# SM3320-BATT-EV.net
KiCad netlist of a schematic drawn in Altium Designer
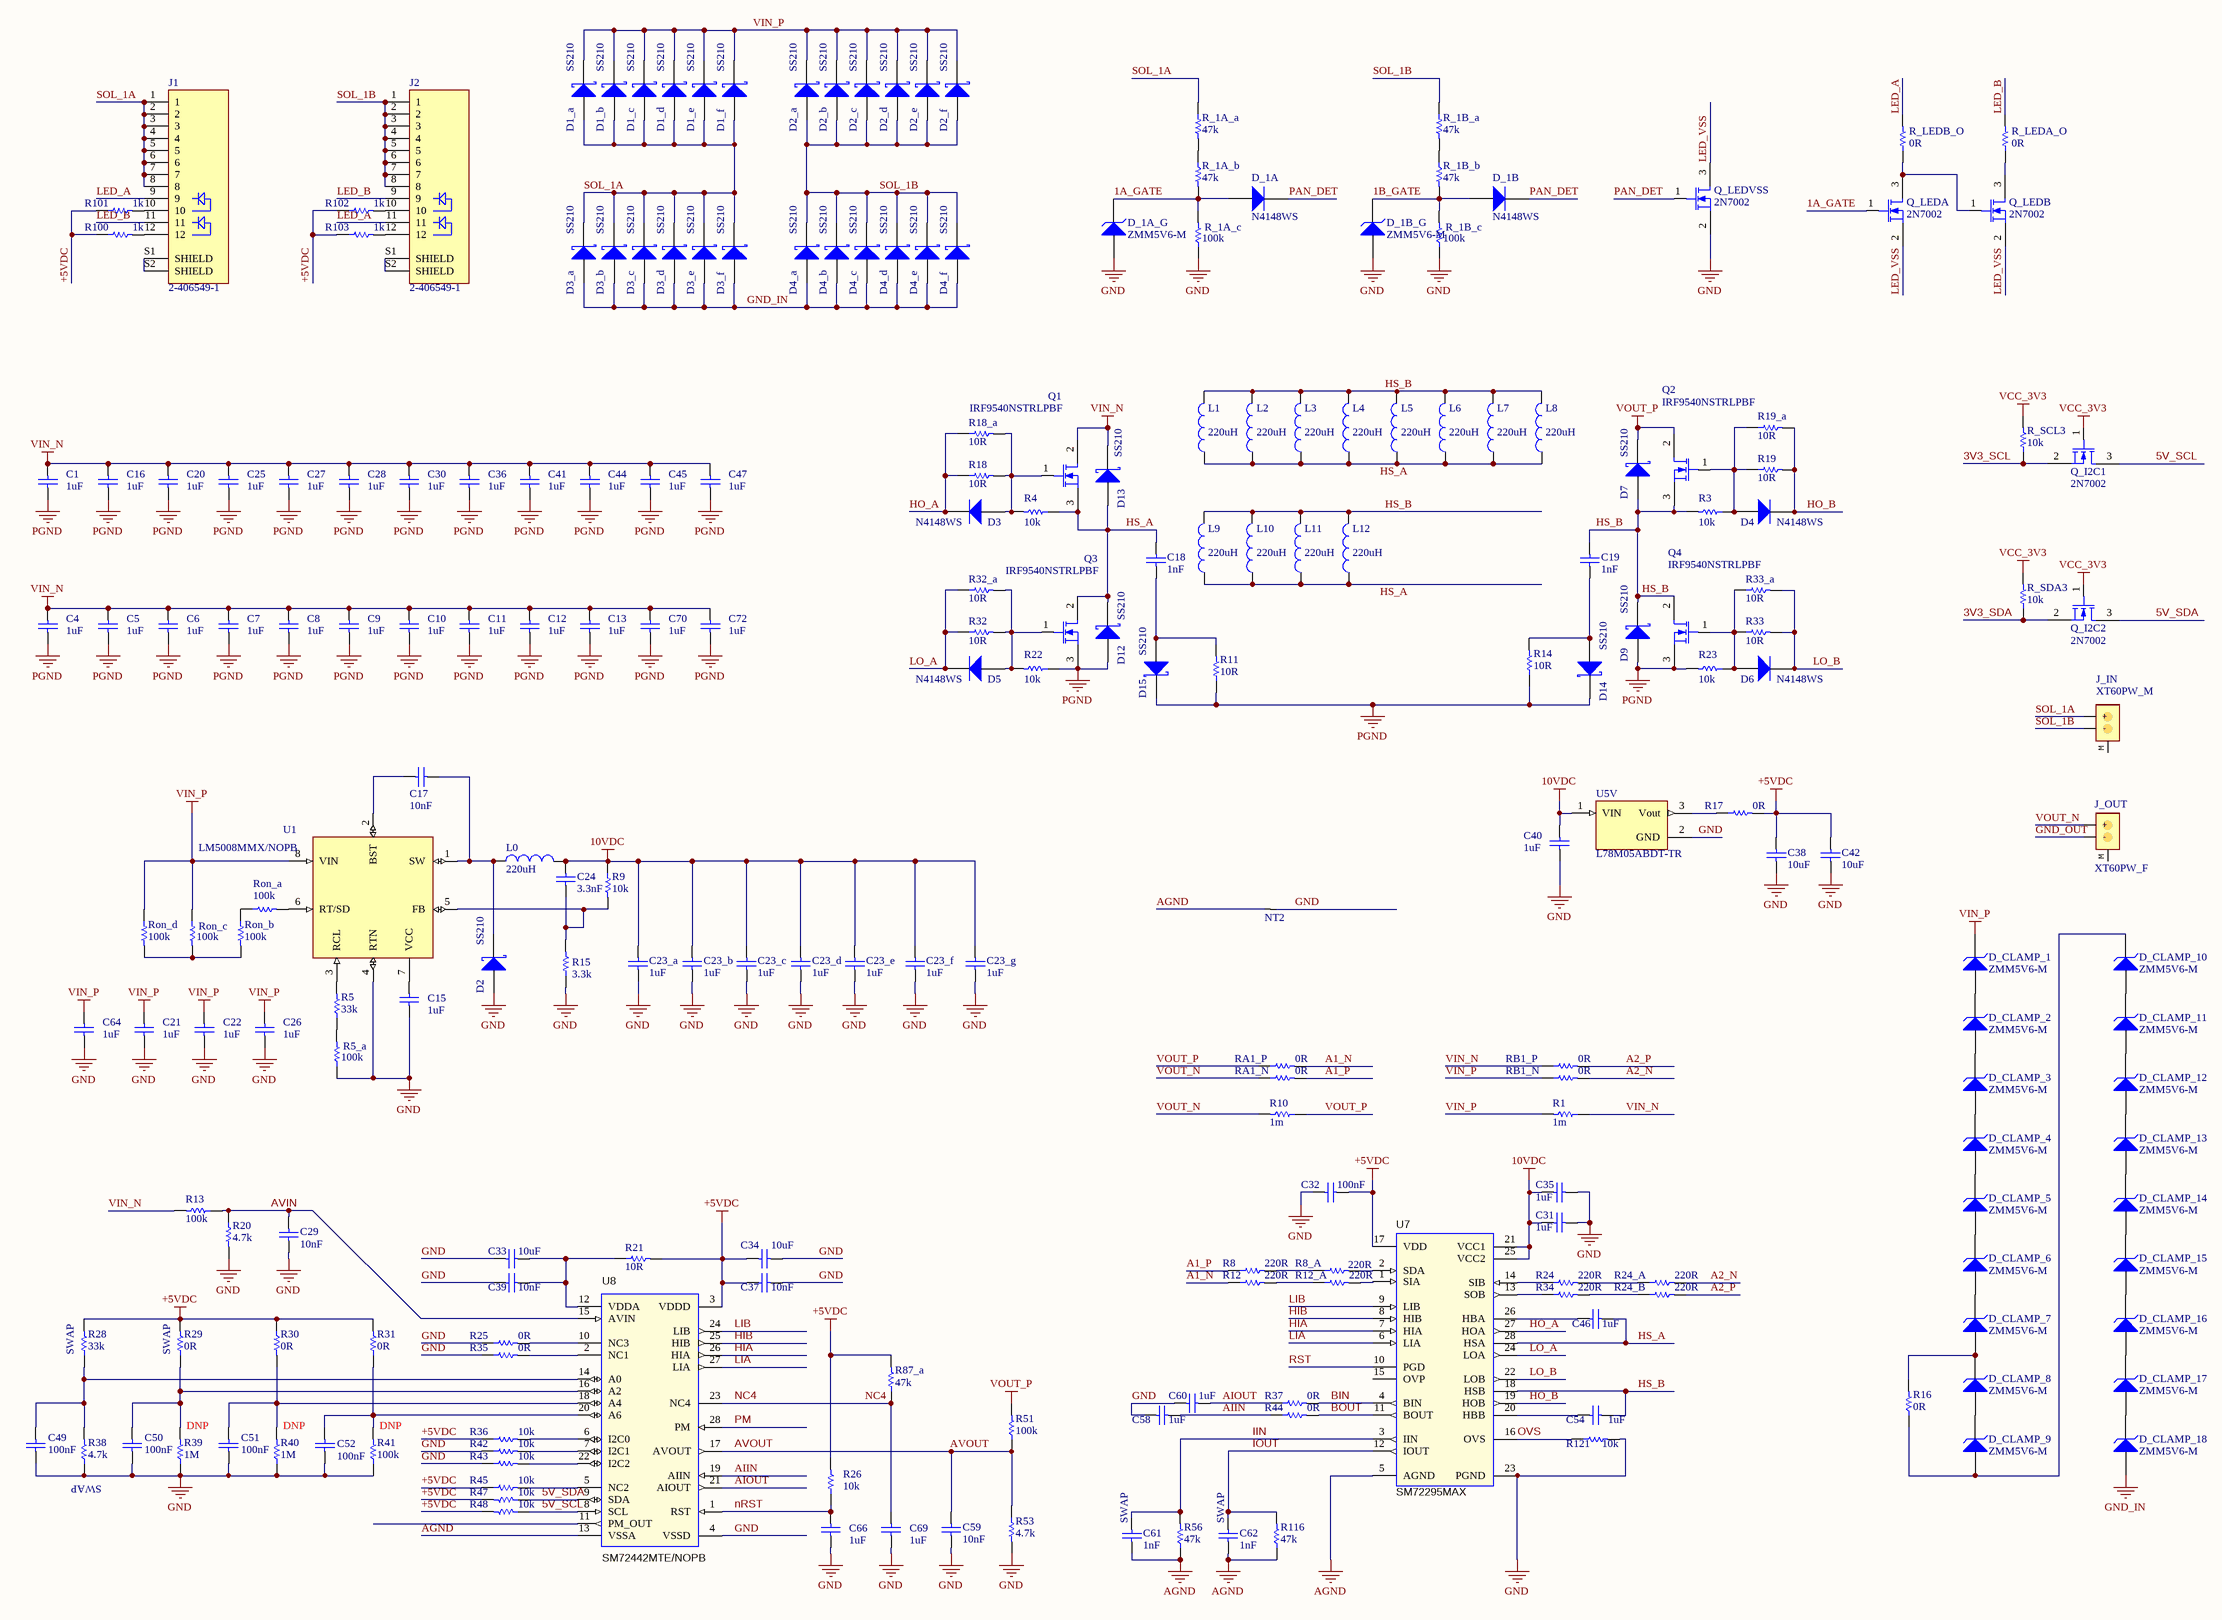
[diagram p0: SM3320-BATT-EV.SchDoc]

(export (version "E")
  (design (tool "Eeschema 10.0.6"))
  (components
    (comp (ref "C1")
      (value "1uF")
      (footprint "C_1206")
      (description "C - CAPACITOR - MLCC - 1uF - 100V - 1206 - X7R")
      (fields (field (name "LCSC PART #") "C91151") (field (name "Comment") "1206B105K101NT"))
      (libsource (lib "JLC_PCB") (part "1206B105K101NT"))
    )
    (comp (ref "C4")
      (value "1uF")
      (footprint "C_1206")
      (description "C - CAPACITOR - MLCC - 1uF - 100V - 1206 - X7R")
      (fields (field (name "LCSC PART #") "C91151") (field (name "Comment") "1206B105K101NT"))
      (libsource (lib "JLC_PCB") (part "1206B105K101NT"))
    )
    (comp (ref "C5")
      (value "1uF")
      (footprint "C_1206")
      (description "C - CAPACITOR - MLCC - 1uF - 100V - 1206 - X7R")
      (fields (field (name "LCSC PART #") "C91151") (field (name "Comment") "1206B105K101NT"))
      (libsource (lib "JLC_PCB") (part "1206B105K101NT"))
    )
    (comp (ref "C6")
      (value "1uF")
      (footprint "C_1206")
      (description "C - CAPACITOR - MLCC - 1uF - 100V - 1206 - X7R")
      (fields (field (name "LCSC PART #") "C91151") (field (name "Comment") "1206B105K101NT"))
      (libsource (lib "JLC_PCB") (part "1206B105K101NT"))
    )
    (comp (ref "C7")
      (value "1uF")
      (footprint "C_1206")
      (description "C - CAPACITOR - MLCC - 1uF - 100V - 1206 - X7R")
      (fields (field (name "LCSC PART #") "C91151") (field (name "Comment") "1206B105K101NT"))
      (libsource (lib "JLC_PCB") (part "1206B105K101NT"))
    )
    (comp (ref "C8")
      (value "1uF")
      (footprint "C_1206")
      (description "C - CAPACITOR - MLCC - 1uF - 100V - 1206 - X7R")
      (fields (field (name "LCSC PART #") "C91151") (field (name "Comment") "1206B105K101NT"))
      (libsource (lib "JLC_PCB") (part "1206B105K101NT"))
    )
    (comp (ref "C9")
      (value "1uF")
      (footprint "C_1206")
      (description "C - CAPACITOR - MLCC - 1uF - 100V - 1206 - X7R")
      (fields (field (name "LCSC PART #") "C91151") (field (name "Comment") "1206B105K101NT"))
      (libsource (lib "JLC_PCB") (part "1206B105K101NT"))
    )
    (comp (ref "C10")
      (value "1uF")
      (footprint "C_1206")
      (description "C - CAPACITOR - MLCC - 1uF - 100V - 1206 - X7R")
      (fields (field (name "LCSC PART #") "C91151") (field (name "Comment") "1206B105K101NT"))
      (libsource (lib "JLC_PCB") (part "1206B105K101NT"))
    )
    (comp (ref "C11")
      (value "1uF")
      (footprint "C_1206")
      (description "C - CAPACITOR - MLCC - 1uF - 100V - 1206 - X7R")
      (fields (field (name "LCSC PART #") "C91151") (field (name "Comment") "1206B105K101NT"))
      (libsource (lib "JLC_PCB") (part "1206B105K101NT"))
    )
    (comp (ref "C12")
      (value "1uF")
      (footprint "C_1206")
      (description "C - CAPACITOR - MLCC - 1uF - 100V - 1206 - X7R")
      (fields (field (name "LCSC PART #") "C91151") (field (name "Comment") "1206B105K101NT"))
      (libsource (lib "JLC_PCB") (part "1206B105K101NT"))
    )
    (comp (ref "C13")
      (value "1uF")
      (footprint "C_1206")
      (description "C - CAPACITOR - MLCC - 1uF - 100V - 1206 - X7R")
      (fields (field (name "LCSC PART #") "C91151") (field (name "Comment") "1206B105K101NT"))
      (libsource (lib "JLC_PCB") (part "1206B105K101NT"))
    )
    (comp (ref "C15")
      (value "1uF")
      (footprint "C_0402")
      (description "C - CAPACITOR - MLCC - 1uF - 25V - 0402")
      (fields (field (name "LCSC PART #") "C52923") (field (name "Comment") "CL05A105KA5NQNC"))
      (libsource (lib "JLC_PCB") (part "CL05A105KA5NQNC"))
    )
    (comp (ref "C16")
      (value "1uF")
      (footprint "C_1206")
      (description "C - CAPACITOR - MLCC - 1uF - 100V - 1206 - X7R")
      (fields (field (name "LCSC PART #") "C91151") (field (name "Comment") "1206B105K101NT"))
      (libsource (lib "JLC_PCB") (part "1206B105K101NT"))
    )
    (comp (ref "C17")
      (value "10nF")
      (footprint "C_0402")
      (description "C - CAPACITOR - MLCC - 10nF - 50V - 0402")
      (fields (field (name "LCSC PART #") "C15195") (field (name "Comment") "CL05B103KB5NNNC"))
      (libsource (lib "JLC_PCB") (part "CL05B103KB5NNNC"))
    )
    (comp (ref "C18")
      (value "1nF")
      (footprint "C_1206")
      (description "C - CAPACITOR - MLCC - 1nF - 2000V - 1206 - X7R")
      (fields (field (name "LCSC PART #") "C9196") (field (name "Comment") "1206B102K202NT"))
      (libsource (lib "JLC_PCB") (part "1206B102K202NT"))
    )
    (comp (ref "C19")
      (value "1nF")
      (footprint "C_1206")
      (description "C - CAPACITOR - MLCC - 1nF - 2000V - 1206 - X7R")
      (fields (field (name "LCSC PART #") "C9196") (field (name "Comment") "1206B102K202NT"))
      (libsource (lib "JLC_PCB") (part "1206B102K202NT"))
    )
    (comp (ref "C20")
      (value "1uF")
      (footprint "C_1206")
      (description "C - CAPACITOR - MLCC - 1uF - 100V - 1206 - X7R")
      (fields (field (name "LCSC PART #") "C91151") (field (name "Comment") "1206B105K101NT"))
      (libsource (lib "JLC_PCB") (part "1206B105K101NT"))
    )
    (comp (ref "C21")
      (value "1uF")
      (footprint "C_1206")
      (description "C - CAPACITOR - MLCC - 1uF - 100V - 1206 - X7R")
      (fields (field (name "LCSC PART #") "C91151") (field (name "Comment") "1206B105K101NT"))
      (libsource (lib "JLC_PCB") (part "1206B105K101NT"))
    )
    (comp (ref "C22")
      (value "1uF")
      (footprint "C_1206")
      (description "C - CAPACITOR - MLCC - 1uF - 100V - 1206 - X7R")
      (fields (field (name "LCSC PART #") "C91151") (field (name "Comment") "1206B105K101NT"))
      (libsource (lib "JLC_PCB") (part "1206B105K101NT"))
    )
    (comp (ref "C23_a")
      (value "1uF")
      (footprint "C_0402")
      (description "C - CAPACITOR - MLCC - 1uF - 25V - 0402")
      (fields (field (name "LCSC PART #") "C52923") (field (name "Comment") "CL05A105KA5NQNC"))
      (libsource (lib "JLC_PCB") (part "CL05A105KA5NQNC"))
    )
    (comp (ref "C23_b")
      (value "1uF")
      (footprint "C_0402")
      (description "C - CAPACITOR - MLCC - 1uF - 25V - 0402")
      (fields (field (name "LCSC PART #") "C52923") (field (name "Comment") "CL05A105KA5NQNC"))
      (libsource (lib "JLC_PCB") (part "CL05A105KA5NQNC"))
    )
    (comp (ref "C23_c")
      (value "1uF")
      (footprint "C_0402")
      (description "C - CAPACITOR - MLCC - 1uF - 25V - 0402")
      (fields (field (name "LCSC PART #") "C52923") (field (name "Comment") "CL05A105KA5NQNC"))
      (libsource (lib "JLC_PCB") (part "CL05A105KA5NQNC"))
    )
    (comp (ref "C23_d")
      (value "1uF")
      (footprint "C_0402")
      (description "C - CAPACITOR - MLCC - 1uF - 25V - 0402")
      (fields (field (name "LCSC PART #") "C52923") (field (name "Comment") "CL05A105KA5NQNC"))
      (libsource (lib "JLC_PCB") (part "CL05A105KA5NQNC"))
    )
    (comp (ref "C23_e")
      (value "1uF")
      (footprint "C_0402")
      (description "C - CAPACITOR - MLCC - 1uF - 25V - 0402")
      (fields (field (name "LCSC PART #") "C52923") (field (name "Comment") "CL05A105KA5NQNC"))
      (libsource (lib "JLC_PCB") (part "CL05A105KA5NQNC"))
    )
    (comp (ref "C23_f")
      (value "1uF")
      (footprint "C_0402")
      (description "C - CAPACITOR - MLCC - 1uF - 25V - 0402")
      (fields (field (name "LCSC PART #") "C52923") (field (name "Comment") "CL05A105KA5NQNC"))
      (libsource (lib "JLC_PCB") (part "CL05A105KA5NQNC"))
    )
    (comp (ref "C23_g")
      (value "1uF")
      (footprint "C_0402")
      (description "C - CAPACITOR - MLCC - 1uF - 25V - 0402")
      (fields (field (name "LCSC PART #") "C52923") (field (name "Comment") "CL05A105KA5NQNC"))
      (libsource (lib "JLC_PCB") (part "CL05A105KA5NQNC"))
    )
    (comp (ref "C24")
      (value "3.3nF")
      (footprint "C_0402")
      (description "C - CAPACITOR - MLCC - 3.3nF - 50V - 0402")
      (fields (field (name "LCSC PART #") "C26404") (field (name "Comment") "CL05B332KB5NNNC"))
      (libsource (lib "JLC_PCB") (part "CL05B332KB5NNNC"))
    )
    (comp (ref "C25")
      (value "1uF")
      (footprint "C_1206")
      (description "C - CAPACITOR - MLCC - 1uF - 100V - 1206 - X7R")
      (fields (field (name "LCSC PART #") "C91151") (field (name "Comment") "1206B105K101NT"))
      (libsource (lib "JLC_PCB") (part "1206B105K101NT"))
    )
    (comp (ref "C26")
      (value "1uF")
      (footprint "C_1206")
      (description "C - CAPACITOR - MLCC - 1uF - 100V - 1206 - X7R")
      (fields (field (name "LCSC PART #") "C91151") (field (name "Comment") "1206B105K101NT"))
      (libsource (lib "JLC_PCB") (part "1206B105K101NT"))
    )
    (comp (ref "C27")
      (value "1uF")
      (footprint "C_1206")
      (description "C - CAPACITOR - MLCC - 1uF - 100V - 1206 - X7R")
      (fields (field (name "LCSC PART #") "C91151") (field (name "Comment") "1206B105K101NT"))
      (libsource (lib "JLC_PCB") (part "1206B105K101NT"))
    )
    (comp (ref "C28")
      (value "1uF")
      (footprint "C_1206")
      (description "C - CAPACITOR - MLCC - 1uF - 100V - 1206 - X7R")
      (fields (field (name "LCSC PART #") "C91151") (field (name "Comment") "1206B105K101NT"))
      (libsource (lib "JLC_PCB") (part "1206B105K101NT"))
    )
    (comp (ref "C29")
      (value "10nF")
      (footprint "C_0402")
      (description "C - CAPACITOR - MLCC - 10nF - 50V - 0402")
      (fields (field (name "LCSC PART #") "C15195") (field (name "Comment") "CL05B103KB5NNNC"))
      (libsource (lib "JLC_PCB") (part "CL05B103KB5NNNC"))
    )
    (comp (ref "C30")
      (value "1uF")
      (footprint "C_1206")
      (description "C - CAPACITOR - MLCC - 1uF - 100V - 1206 - X7R")
      (fields (field (name "LCSC PART #") "C91151") (field (name "Comment") "1206B105K101NT"))
      (libsource (lib "JLC_PCB") (part "1206B105K101NT"))
    )
    (comp (ref "C31")
      (value "1uF")
      (footprint "C_0402")
      (description "C - CAPACITOR - MLCC - 1uF - 25V - 0402")
      (fields (field (name "LCSC PART #") "C52923") (field (name "Comment") "CL05A105KA5NQNC"))
      (libsource (lib "JLC_PCB") (part "CL05A105KA5NQNC"))
    )
    (comp (ref "C32")
      (value "100nF")
      (footprint "C_0402")
      (description "C - CAPACITOR - MLCC - 100nF - 16V - 0402")
      (fields (field (name "LCSC PART #") "C1525") (field (name "Comment") "CL05B104KO5NNNC"))
      (libsource (lib "JLC_PCB") (part "CL05B104KO5NNNC"))
    )
    (comp (ref "C33")
      (value "10uF")
      (footprint "C_0402")
      (description "C - CAPACITOR - MLCC - 10uF - 6.3V - 0402")
      (fields (field (name "LCSC PART #") "C15525") (field (name "Comment") "CL05A106MQ5NUNC"))
      (libsource (lib "JLC_PCB") (part "CL05A106MQ5NUNC"))
    )
    (comp (ref "C34")
      (value "10uF")
      (footprint "C_0402")
      (description "C - CAPACITOR - MLCC - 10uF - 6.3V - 0402")
      (fields (field (name "LCSC PART #") "C15525") (field (name "Comment") "CL05A106MQ5NUNC"))
      (libsource (lib "JLC_PCB") (part "CL05A106MQ5NUNC"))
    )
    (comp (ref "C35")
      (value "1uF")
      (footprint "C_0402")
      (description "C - CAPACITOR - MLCC - 1uF - 25V - 0402")
      (fields (field (name "LCSC PART #") "C52923") (field (name "Comment") "CL05A105KA5NQNC"))
      (libsource (lib "JLC_PCB") (part "CL05A105KA5NQNC"))
    )
    (comp (ref "C36")
      (value "1uF")
      (footprint "C_1206")
      (description "C - CAPACITOR - MLCC - 1uF - 100V - 1206 - X7R")
      (fields (field (name "LCSC PART #") "C91151") (field (name "Comment") "1206B105K101NT"))
      (libsource (lib "JLC_PCB") (part "1206B105K101NT"))
    )
    (comp (ref "C37")
      (value "10nF")
      (footprint "C_0402")
      (description "C - CAPACITOR - MLCC - 10nF - 50V - 0402")
      (fields (field (name "LCSC PART #") "C15195") (field (name "Comment") "CL05B103KB5NNNC"))
      (libsource (lib "JLC_PCB") (part "CL05B103KB5NNNC"))
    )
    (comp (ref "C38")
      (value "10uF")
      (footprint "C_0402")
      (description "C - CAPACITOR - MLCC - 10uF - 6.3V - 0402")
      (fields (field (name "LCSC PART #") "C15525") (field (name "Comment") "CL05A106MQ5NUNC"))
      (libsource (lib "JLC_PCB") (part "CL05A106MQ5NUNC"))
    )
    (comp (ref "C39")
      (value "10nF")
      (footprint "C_0402")
      (description "C - CAPACITOR - MLCC - 10nF - 50V - 0402")
      (fields (field (name "LCSC PART #") "C15195") (field (name "Comment") "CL05B103KB5NNNC"))
      (libsource (lib "JLC_PCB") (part "CL05B103KB5NNNC"))
    )
    (comp (ref "C40")
      (value "1uF")
      (footprint "C_0402")
      (description "C - CAPACITOR - MLCC - 1uF - 25V - 0402")
      (fields (field (name "LCSC PART #") "C52923") (field (name "Comment") "CL05A105KA5NQNC"))
      (libsource (lib "JLC_PCB") (part "CL05A105KA5NQNC"))
    )
    (comp (ref "C41")
      (value "1uF")
      (footprint "C_1206")
      (description "C - CAPACITOR - MLCC - 1uF - 100V - 1206 - X7R")
      (fields (field (name "LCSC PART #") "C91151") (field (name "Comment") "1206B105K101NT"))
      (libsource (lib "JLC_PCB") (part "1206B105K101NT"))
    )
    (comp (ref "C42")
      (value "10uF")
      (footprint "C_0402")
      (description "C - CAPACITOR - MLCC - 10uF - 6.3V - 0402")
      (fields (field (name "LCSC PART #") "C15525") (field (name "Comment") "CL05A106MQ5NUNC"))
      (libsource (lib "JLC_PCB") (part "CL05A106MQ5NUNC"))
    )
    (comp (ref "C44")
      (value "1uF")
      (footprint "C_1206")
      (description "C - CAPACITOR - MLCC - 1uF - 100V - 1206 - X7R")
      (fields (field (name "LCSC PART #") "C91151") (field (name "Comment") "1206B105K101NT"))
      (libsource (lib "JLC_PCB") (part "1206B105K101NT"))
    )
    (comp (ref "C45")
      (value "1uF")
      (footprint "C_1206")
      (description "C - CAPACITOR - MLCC - 1uF - 100V - 1206 - X7R")
      (fields (field (name "LCSC PART #") "C91151") (field (name "Comment") "1206B105K101NT"))
      (libsource (lib "JLC_PCB") (part "1206B105K101NT"))
    )
    (comp (ref "C46")
      (value "1uF")
      (footprint "C_0402")
      (description "C - CAPACITOR - MLCC - 1uF - 25V - 0402")
      (fields (field (name "LCSC PART #") "C52923") (field (name "Comment") "CL05A105KA5NQNC"))
      (libsource (lib "JLC_PCB") (part "CL05A105KA5NQNC"))
    )
    (comp (ref "C47")
      (value "1uF")
      (footprint "C_1206")
      (description "C - CAPACITOR - MLCC - 1uF - 100V - 1206 - X7R")
      (fields (field (name "LCSC PART #") "C91151") (field (name "Comment") "1206B105K101NT"))
      (libsource (lib "JLC_PCB") (part "1206B105K101NT"))
    )
    (comp (ref "C49")
      (value "100nF")
      (footprint "C_0402")
      (description "C - CAPACITOR - MLCC - 100nF - 16V - 0402")
      (fields (field (name "LCSC PART #") "C1525") (field (name "Comment") "CL05B104KO5NNNC"))
      (libsource (lib "JLC_PCB") (part "CL05B104KO5NNNC"))
    )
    (comp (ref "C50")
      (value "100nF")
      (footprint "C_0402")
      (description "C - CAPACITOR - MLCC - 100nF - 16V - 0402")
      (fields (field (name "LCSC PART #") "C1525") (field (name "Comment") "CL05B104KO5NNNC"))
      (libsource (lib "JLC_PCB") (part "CL05B104KO5NNNC"))
    )
    (comp (ref "C51")
      (value "100nF")
      (footprint "C_0402")
      (description "C - CAPACITOR - MLCC - 100nF - 16V - 0402")
      (fields (field (name "LCSC PART #") "C1525") (field (name "Comment") "CL05B104KO5NNNC"))
      (libsource (lib "JLC_PCB") (part "CL05B104KO5NNNC"))
    )
    (comp (ref "C52")
      (value "100nF")
      (footprint "C_0402")
      (description "C - CAPACITOR - MLCC - 100nF - 16V - 0402")
      (fields (field (name "LCSC PART #") "C1525") (field (name "Comment") "CL05B104KO5NNNC"))
      (libsource (lib "JLC_PCB") (part "CL05B104KO5NNNC"))
    )
    (comp (ref "C54")
      (value "1uF")
      (footprint "C_0402")
      (description "C - CAPACITOR - MLCC - 1uF - 25V - 0402")
      (fields (field (name "LCSC PART #") "C52923") (field (name "Comment") "CL05A105KA5NQNC"))
      (libsource (lib "JLC_PCB") (part "CL05A105KA5NQNC"))
    )
    (comp (ref "C58")
      (value "1uF")
      (footprint "C_0402")
      (description "C - CAPACITOR - MLCC - 1uF - 25V - 0402")
      (fields (field (name "LCSC PART #") "C52923") (field (name "Comment") "CL05A105KA5NQNC"))
      (libsource (lib "JLC_PCB") (part "CL05A105KA5NQNC"))
    )
    (comp (ref "C59")
      (value "10nF")
      (footprint "C_0402")
      (description "C - CAPACITOR - MLCC - 10nF - 50V - 0402")
      (fields (field (name "LCSC PART #") "C15195") (field (name "Comment") "CL05B103KB5NNNC"))
      (libsource (lib "JLC_PCB") (part "CL05B103KB5NNNC"))
    )
    (comp (ref "C60")
      (value "1uF")
      (footprint "C_0402")
      (description "C - CAPACITOR - MLCC - 1uF - 25V - 0402")
      (fields (field (name "LCSC PART #") "C52923") (field (name "Comment") "CL05A105KA5NQNC"))
      (libsource (lib "JLC_PCB") (part "CL05A105KA5NQNC"))
    )
    (comp (ref "C61")
      (value "1nF")
      (footprint "C_0402")
      (description "C - CAPACITOR - MLCC - 1nF - 50V - 0402")
      (fields (field (name "LCSC PART #") "C1523") (field (name "Comment") "0402B102K500NT"))
      (libsource (lib "JLC_PCB") (part "0402B102K500NT"))
    )
    (comp (ref "C62")
      (value "1nF")
      (footprint "C_0402")
      (description "C - CAPACITOR - MLCC - 1nF - 50V - 0402")
      (fields (field (name "LCSC PART #") "C1523") (field (name "Comment") "0402B102K500NT"))
      (libsource (lib "JLC_PCB") (part "0402B102K500NT"))
    )
    (comp (ref "C64")
      (value "1uF")
      (footprint "C_1206")
      (description "C - CAPACITOR - MLCC - 1uF - 100V - 1206 - X7R")
      (fields (field (name "LCSC PART #") "C91151") (field (name "Comment") "1206B105K101NT"))
      (libsource (lib "JLC_PCB") (part "1206B105K101NT"))
    )
    (comp (ref "C66")
      (value "1uF")
      (footprint "C_0402")
      (description "C - CAPACITOR - MLCC - 1uF - 25V - 0402")
      (fields (field (name "LCSC PART #") "C52923") (field (name "Comment") "CL05A105KA5NQNC"))
      (libsource (lib "JLC_PCB") (part "CL05A105KA5NQNC"))
    )
    (comp (ref "C69")
      (value "1uF")
      (footprint "C_0402")
      (description "C - CAPACITOR - MLCC - 1uF - 25V - 0402")
      (fields (field (name "LCSC PART #") "C52923") (field (name "Comment") "CL05A105KA5NQNC"))
      (libsource (lib "JLC_PCB") (part "CL05A105KA5NQNC"))
    )
    (comp (ref "C70")
      (value "1uF")
      (footprint "C_1206")
      (description "C - CAPACITOR - MLCC - 1uF - 100V - 1206 - X7R")
      (fields (field (name "LCSC PART #") "C91151") (field (name "Comment") "1206B105K101NT"))
      (libsource (lib "JLC_PCB") (part "1206B105K101NT"))
    )
    (comp (ref "C72")
      (value "1uF")
      (footprint "C_1206")
      (description "C - CAPACITOR - MLCC - 1uF - 100V - 1206 - X7R")
      (fields (field (name "LCSC PART #") "C91151") (field (name "Comment") "1206B105K101NT"))
      (libsource (lib "JLC_PCB") (part "1206B105K101NT"))
    )
    (comp (ref "D1_a")
      (value "SS210")
      (footprint "DO-214AC")
      (description "D - DIODE - SCHOTTKY - 100V - 2A")
      (fields (field (name "LCSC PART #") "C14996"))
      (libsource (lib "JLC_PCB") (part "SS210"))
    )
    (comp (ref "D1_b")
      (value "SS210")
      (footprint "DO-214AC")
      (description "D - DIODE - SCHOTTKY - 100V - 2A")
      (fields (field (name "LCSC PART #") "C14996"))
      (libsource (lib "JLC_PCB") (part "SS210"))
    )
    (comp (ref "D1_c")
      (value "SS210")
      (footprint "DO-214AC")
      (description "D - DIODE - SCHOTTKY - 100V - 2A")
      (fields (field (name "LCSC PART #") "C14996"))
      (libsource (lib "JLC_PCB") (part "SS210"))
    )
    (comp (ref "D1_d")
      (value "SS210")
      (footprint "DO-214AC")
      (description "D - DIODE - SCHOTTKY - 100V - 2A")
      (fields (field (name "LCSC PART #") "C14996"))
      (libsource (lib "JLC_PCB") (part "SS210"))
    )
    (comp (ref "D1_e")
      (value "SS210")
      (footprint "DO-214AC")
      (description "D - DIODE - SCHOTTKY - 100V - 2A")
      (fields (field (name "LCSC PART #") "C14996"))
      (libsource (lib "JLC_PCB") (part "SS210"))
    )
    (comp (ref "D1_f")
      (value "SS210")
      (footprint "DO-214AC")
      (description "D - DIODE - SCHOTTKY - 100V - 2A")
      (fields (field (name "LCSC PART #") "C14996"))
      (libsource (lib "JLC_PCB") (part "SS210"))
    )
    (comp (ref "D2")
      (value "SS210")
      (footprint "DO-214AC")
      (description "D - DIODE - SCHOTTKY - 100V - 2A")
      (fields (field (name "LCSC PART #") "C14996"))
      (libsource (lib "JLC_PCB") (part "SS210"))
    )
    (comp (ref "D2_a")
      (value "SS210")
      (footprint "DO-214AC")
      (description "D - DIODE - SCHOTTKY - 100V - 2A")
      (fields (field (name "LCSC PART #") "C14996"))
      (libsource (lib "JLC_PCB") (part "SS210"))
    )
    (comp (ref "D2_b")
      (value "SS210")
      (footprint "DO-214AC")
      (description "D - DIODE - SCHOTTKY - 100V - 2A")
      (fields (field (name "LCSC PART #") "C14996"))
      (libsource (lib "JLC_PCB") (part "SS210"))
    )
    (comp (ref "D2_c")
      (value "SS210")
      (footprint "DO-214AC")
      (description "D - DIODE - SCHOTTKY - 100V - 2A")
      (fields (field (name "LCSC PART #") "C14996"))
      (libsource (lib "JLC_PCB") (part "SS210"))
    )
    (comp (ref "D2_d")
      (value "SS210")
      (footprint "DO-214AC")
      (description "D - DIODE - SCHOTTKY - 100V - 2A")
      (fields (field (name "LCSC PART #") "C14996"))
      (libsource (lib "JLC_PCB") (part "SS210"))
    )
    (comp (ref "D2_e")
      (value "SS210")
      (footprint "DO-214AC")
      (description "D - DIODE - SCHOTTKY - 100V - 2A")
      (fields (field (name "LCSC PART #") "C14996"))
      (libsource (lib "JLC_PCB") (part "SS210"))
    )
    (comp (ref "D2_f")
      (value "SS210")
      (footprint "DO-214AC")
      (description "D - DIODE - SCHOTTKY - 100V - 2A")
      (fields (field (name "LCSC PART #") "C14996"))
      (libsource (lib "JLC_PCB") (part "SS210"))
    )
    (comp (ref "D3")
      (value "N4148WS")
      (footprint "SOD-323")
      (description "D - DIODE - FAST TRR - 100V - 150mA - 4ns")
      (fields (field (name "LCSC PART #") "C2128"))
      (libsource (lib "JLC_PCB") (part "N4148WS"))
    )
    (comp (ref "D3_a")
      (value "SS210")
      (footprint "DO-214AC")
      (description "D - DIODE - SCHOTTKY - 100V - 2A")
      (fields (field (name "LCSC PART #") "C14996"))
      (libsource (lib "JLC_PCB") (part "SS210"))
    )
    (comp (ref "D3_b")
      (value "SS210")
      (footprint "DO-214AC")
      (description "D - DIODE - SCHOTTKY - 100V - 2A")
      (fields (field (name "LCSC PART #") "C14996"))
      (libsource (lib "JLC_PCB") (part "SS210"))
    )
    (comp (ref "D3_c")
      (value "SS210")
      (footprint "DO-214AC")
      (description "D - DIODE - SCHOTTKY - 100V - 2A")
      (fields (field (name "LCSC PART #") "C14996"))
      (libsource (lib "JLC_PCB") (part "SS210"))
    )
    (comp (ref "D3_d")
      (value "SS210")
      (footprint "DO-214AC")
      (description "D - DIODE - SCHOTTKY - 100V - 2A")
      (fields (field (name "LCSC PART #") "C14996"))
      (libsource (lib "JLC_PCB") (part "SS210"))
    )
    (comp (ref "D3_e")
      (value "SS210")
      (footprint "DO-214AC")
      (description "D - DIODE - SCHOTTKY - 100V - 2A")
      (fields (field (name "LCSC PART #") "C14996"))
      (libsource (lib "JLC_PCB") (part "SS210"))
    )
    (comp (ref "D3_f")
      (value "SS210")
      (footprint "DO-214AC")
      (description "D - DIODE - SCHOTTKY - 100V - 2A")
      (fields (field (name "LCSC PART #") "C14996"))
      (libsource (lib "JLC_PCB") (part "SS210"))
    )
    (comp (ref "D4")
      (value "N4148WS")
      (footprint "SOD-323")
      (description "D - DIODE - FAST TRR - 100V - 150mA - 4ns")
      (fields (field (name "LCSC PART #") "C2128"))
      (libsource (lib "JLC_PCB") (part "N4148WS"))
    )
    (comp (ref "D4_a")
      (value "SS210")
      (footprint "DO-214AC")
      (description "D - DIODE - SCHOTTKY - 100V - 2A")
      (fields (field (name "LCSC PART #") "C14996"))
      (libsource (lib "JLC_PCB") (part "SS210"))
    )
    (comp (ref "D4_b")
      (value "SS210")
      (footprint "DO-214AC")
      (description "D - DIODE - SCHOTTKY - 100V - 2A")
      (fields (field (name "LCSC PART #") "C14996"))
      (libsource (lib "JLC_PCB") (part "SS210"))
    )
    (comp (ref "D4_c")
      (value "SS210")
      (footprint "DO-214AC")
      (description "D - DIODE - SCHOTTKY - 100V - 2A")
      (fields (field (name "LCSC PART #") "C14996"))
      (libsource (lib "JLC_PCB") (part "SS210"))
    )
    (comp (ref "D4_d")
      (value "SS210")
      (footprint "DO-214AC")
      (description "D - DIODE - SCHOTTKY - 100V - 2A")
      (fields (field (name "LCSC PART #") "C14996"))
      (libsource (lib "JLC_PCB") (part "SS210"))
    )
    (comp (ref "D4_e")
      (value "SS210")
      (footprint "DO-214AC")
      (description "D - DIODE - SCHOTTKY - 100V - 2A")
      (fields (field (name "LCSC PART #") "C14996"))
      (libsource (lib "JLC_PCB") (part "SS210"))
    )
    (comp (ref "D4_f")
      (value "SS210")
      (footprint "DO-214AC")
      (description "D - DIODE - SCHOTTKY - 100V - 2A")
      (fields (field (name "LCSC PART #") "C14996"))
      (libsource (lib "JLC_PCB") (part "SS210"))
    )
    (comp (ref "D5")
      (value "N4148WS")
      (footprint "SOD-323")
      (description "D - DIODE - FAST TRR - 100V - 150mA - 4ns")
      (fields (field (name "LCSC PART #") "C2128"))
      (libsource (lib "JLC_PCB") (part "N4148WS"))
    )
    (comp (ref "D6")
      (value "N4148WS")
      (footprint "SOD-323")
      (description "D - DIODE - FAST TRR - 100V - 150mA - 4ns")
      (fields (field (name "LCSC PART #") "C2128"))
      (libsource (lib "JLC_PCB") (part "N4148WS"))
    )
    (comp (ref "D7")
      (value "SS210")
      (footprint "DO-214AC")
      (description "D - DIODE - SCHOTTKY - 100V - 2A")
      (fields (field (name "LCSC PART #") "C14996"))
      (libsource (lib "JLC_PCB") (part "SS210"))
    )
    (comp (ref "D9")
      (value "SS210")
      (footprint "DO-214AC")
      (description "D - DIODE - SCHOTTKY - 100V - 2A")
      (fields (field (name "LCSC PART #") "C14996"))
      (libsource (lib "JLC_PCB") (part "SS210"))
    )
    (comp (ref "D12")
      (value "SS210")
      (footprint "DO-214AC")
      (description "D - DIODE - SCHOTTKY - 100V - 2A")
      (fields (field (name "LCSC PART #") "C14996"))
      (libsource (lib "JLC_PCB") (part "SS210"))
    )
    (comp (ref "D13")
      (value "SS210")
      (footprint "DO-214AC")
      (description "D - DIODE - SCHOTTKY - 100V - 2A")
      (fields (field (name "LCSC PART #") "C14996"))
      (libsource (lib "JLC_PCB") (part "SS210"))
    )
    (comp (ref "D14")
      (value "SS210")
      (footprint "DO-214AC")
      (description "D - DIODE - SCHOTTKY - 100V - 2A")
      (fields (field (name "LCSC PART #") "C14996"))
      (libsource (lib "JLC_PCB") (part "SS210"))
    )
    (comp (ref "D15")
      (value "SS210")
      (footprint "DO-214AC")
      (description "D - DIODE - SCHOTTKY - 100V - 2A")
      (fields (field (name "LCSC PART #") "C14996"))
      (libsource (lib "JLC_PCB") (part "SS210"))
    )
    (comp (ref "D_1A")
      (value "N4148WS")
      (footprint "SOD-323")
      (description "D - DIODE - FAST TRR - 100V - 150mA - 4ns")
      (fields (field (name "LCSC PART #") "C2128"))
      (libsource (lib "JLC_PCB") (part "N4148WS"))
    )
    (comp (ref "D_1A_G")
      (value "ZMM5V6-M")
      (footprint "DO-213AA")
      (description "D - DIODE - ZENER - 5.6V - 500mW")
      (fields (field (name "LCSC PART #") "C8062"))
      (libsource (lib "JLC_PCB") (part "ZMM5V6-M"))
    )
    (comp (ref "D_1B")
      (value "N4148WS")
      (footprint "SOD-323")
      (description "D - DIODE - FAST TRR - 100V - 150mA - 4ns")
      (fields (field (name "LCSC PART #") "C2128"))
      (libsource (lib "JLC_PCB") (part "N4148WS"))
    )
    (comp (ref "D_1B_G")
      (value "ZMM5V6-M")
      (footprint "DO-213AA")
      (description "D - DIODE - ZENER - 5.6V - 500mW")
      (fields (field (name "LCSC PART #") "C8062"))
      (libsource (lib "JLC_PCB") (part "ZMM5V6-M"))
    )
    (comp (ref "D_CLAMP_1")
      (value "ZMM5V6-M")
      (footprint "DO-213AA")
      (description "D - DIODE - ZENER - 5.6V - 500mW")
      (fields (field (name "LCSC PART #") "C8062"))
      (libsource (lib "JLC_PCB") (part "ZMM5V6-M"))
    )
    (comp (ref "D_CLAMP_2")
      (value "ZMM5V6-M")
      (footprint "DO-213AA")
      (description "D - DIODE - ZENER - 5.6V - 500mW")
      (fields (field (name "LCSC PART #") "C8062"))
      (libsource (lib "JLC_PCB") (part "ZMM5V6-M"))
    )
    (comp (ref "D_CLAMP_3")
      (value "ZMM5V6-M")
      (footprint "DO-213AA")
      (description "D - DIODE - ZENER - 5.6V - 500mW")
      (fields (field (name "LCSC PART #") "C8062"))
      (libsource (lib "JLC_PCB") (part "ZMM5V6-M"))
    )
    (comp (ref "D_CLAMP_4")
      (value "ZMM5V6-M")
      (footprint "DO-213AA")
      (description "D - DIODE - ZENER - 5.6V - 500mW")
      (fields (field (name "LCSC PART #") "C8062"))
      (libsource (lib "JLC_PCB") (part "ZMM5V6-M"))
    )
    (comp (ref "D_CLAMP_5")
      (value "ZMM5V6-M")
      (footprint "DO-213AA")
      (description "D - DIODE - ZENER - 5.6V - 500mW")
      (fields (field (name "LCSC PART #") "C8062"))
      (libsource (lib "JLC_PCB") (part "ZMM5V6-M"))
    )
    (comp (ref "D_CLAMP_6")
      (value "ZMM5V6-M")
      (footprint "DO-213AA")
      (description "D - DIODE - ZENER - 5.6V - 500mW")
      (fields (field (name "LCSC PART #") "C8062"))
      (libsource (lib "JLC_PCB") (part "ZMM5V6-M"))
    )
    (comp (ref "D_CLAMP_7")
      (value "ZMM5V6-M")
      (footprint "DO-213AA")
      (description "D - DIODE - ZENER - 5.6V - 500mW")
      (fields (field (name "LCSC PART #") "C8062"))
      (libsource (lib "JLC_PCB") (part "ZMM5V6-M"))
    )
    (comp (ref "D_CLAMP_8")
      (value "ZMM5V6-M")
      (footprint "DO-213AA")
      (description "D - DIODE - ZENER - 5.6V - 500mW")
      (fields (field (name "LCSC PART #") "C8062"))
      (libsource (lib "JLC_PCB") (part "ZMM5V6-M"))
    )
    (comp (ref "D_CLAMP_9")
      (value "ZMM5V6-M")
      (footprint "DO-213AA")
      (description "D - DIODE - ZENER - 5.6V - 500mW")
      (fields (field (name "LCSC PART #") "C8062"))
      (libsource (lib "JLC_PCB") (part "ZMM5V6-M"))
    )
    (comp (ref "D_CLAMP_10")
      (value "ZMM5V6-M")
      (footprint "DO-213AA")
      (description "D - DIODE - ZENER - 5.6V - 500mW")
      (fields (field (name "LCSC PART #") "C8062"))
      (libsource (lib "JLC_PCB") (part "ZMM5V6-M"))
    )
    (comp (ref "D_CLAMP_11")
      (value "ZMM5V6-M")
      (footprint "DO-213AA")
      (description "D - DIODE - ZENER - 5.6V - 500mW")
      (fields (field (name "LCSC PART #") "C8062"))
      (libsource (lib "JLC_PCB") (part "ZMM5V6-M"))
    )
    (comp (ref "D_CLAMP_12")
      (value "ZMM5V6-M")
      (footprint "DO-213AA")
      (description "D - DIODE - ZENER - 5.6V - 500mW")
      (fields (field (name "LCSC PART #") "C8062"))
      (libsource (lib "JLC_PCB") (part "ZMM5V6-M"))
    )
    (comp (ref "D_CLAMP_13")
      (value "ZMM5V6-M")
      (footprint "DO-213AA")
      (description "D - DIODE - ZENER - 5.6V - 500mW")
      (fields (field (name "LCSC PART #") "C8062"))
      (libsource (lib "JLC_PCB") (part "ZMM5V6-M"))
    )
    (comp (ref "D_CLAMP_14")
      (value "ZMM5V6-M")
      (footprint "DO-213AA")
      (description "D - DIODE - ZENER - 5.6V - 500mW")
      (fields (field (name "LCSC PART #") "C8062"))
      (libsource (lib "JLC_PCB") (part "ZMM5V6-M"))
    )
    (comp (ref "D_CLAMP_15")
      (value "ZMM5V6-M")
      (footprint "DO-213AA")
      (description "D - DIODE - ZENER - 5.6V - 500mW")
      (fields (field (name "LCSC PART #") "C8062"))
      (libsource (lib "JLC_PCB") (part "ZMM5V6-M"))
    )
    (comp (ref "D_CLAMP_16")
      (value "ZMM5V6-M")
      (footprint "DO-213AA")
      (description "D - DIODE - ZENER - 5.6V - 500mW")
      (fields (field (name "LCSC PART #") "C8062"))
      (libsource (lib "JLC_PCB") (part "ZMM5V6-M"))
    )
    (comp (ref "D_CLAMP_17")
      (value "ZMM5V6-M")
      (footprint "DO-213AA")
      (description "D - DIODE - ZENER - 5.6V - 500mW")
      (fields (field (name "LCSC PART #") "C8062"))
      (libsource (lib "JLC_PCB") (part "ZMM5V6-M"))
    )
    (comp (ref "D_CLAMP_18")
      (value "ZMM5V6-M")
      (footprint "DO-213AA")
      (description "D - DIODE - ZENER - 5.6V - 500mW")
      (fields (field (name "LCSC PART #") "C8062"))
      (libsource (lib "JLC_PCB") (part "ZMM5V6-M"))
    )
    (comp (ref "J1")
      (value "2-406549-1")
      (footprint "TE_2-406549-1")
      (description "J - JACK - ETHERNET - Right - THT")
      (fields (field (name "LCSC PART #") "C125068"))
      (libsource (lib "JLC_PCB") (part "2-406549-1"))
    )
    (comp (ref "J2")
      (value "2-406549-1")
      (footprint "TE_2-406549-1")
      (description "J - JACK - ETHERNET - Right - THT")
      (fields (field (name "LCSC PART #") "C125068"))
      (libsource (lib "JLC_PCB") (part "2-406549-1"))
    )
    (comp (ref "J_IN")
      (value "XT60PW_M")
      (footprint "XT60PW_M")
      (description "J - JACK - POWER - XT60 - RIGHT - MALE")
      (fields (field (name "LCSC PART #") "X"))
      (libsource (lib "JLC_PCB") (part "XT60PW_M"))
    )
    (comp (ref "J_OUT")
      (value "XT60PW_F")
      (footprint "XT60PW_F")
      (description "J - JACK - POWER - XT60 - RIGHT - FEMALE")
      (fields (field (name "LCSC PART #") "X"))
      (libsource (lib "JLC_PCB") (part "XT60PW_F"))
    )
    (comp (ref "L0")
      (value "220uH")
      (footprint "SRR1260")
      (description "L - INDUCTOR - 220uH - 1.6A - 12.5mm")
      (fields (field (name "LCSC PART #") "C169380") (field (name "Comment") "SWRB1207S-221MT"))
      (libsource (lib "JLC_PCB") (part "SWRB1207S-221MT"))
    )
    (comp (ref "L1")
      (value "220uH")
      (footprint "SRR1260")
      (description "L - INDUCTOR - 220uH - 1.6A - 12.5mm")
      (fields (field (name "LCSC PART #") "C169380") (field (name "Comment") "SWRB1207S-221MT"))
      (libsource (lib "JLC_PCB") (part "SWRB1207S-221MT"))
    )
    (comp (ref "L2")
      (value "220uH")
      (footprint "SRR1260")
      (description "L - INDUCTOR - 220uH - 1.6A - 12.5mm")
      (fields (field (name "LCSC PART #") "C169380") (field (name "Comment") "SWRB1207S-221MT"))
      (libsource (lib "JLC_PCB") (part "SWRB1207S-221MT"))
    )
    (comp (ref "L3")
      (value "220uH")
      (footprint "SRR1260")
      (description "L - INDUCTOR - 220uH - 1.6A - 12.5mm")
      (fields (field (name "LCSC PART #") "C169380") (field (name "Comment") "SWRB1207S-221MT"))
      (libsource (lib "JLC_PCB") (part "SWRB1207S-221MT"))
    )
    (comp (ref "L4")
      (value "220uH")
      (footprint "SRR1260")
      (description "L - INDUCTOR - 220uH - 1.6A - 12.5mm")
      (fields (field (name "LCSC PART #") "C169380") (field (name "Comment") "SWRB1207S-221MT"))
      (libsource (lib "JLC_PCB") (part "SWRB1207S-221MT"))
    )
    (comp (ref "L5")
      (value "220uH")
      (footprint "SRR1260")
      (description "L - INDUCTOR - 220uH - 1.6A - 12.5mm")
      (fields (field (name "LCSC PART #") "C169380") (field (name "Comment") "SWRB1207S-221MT"))
      (libsource (lib "JLC_PCB") (part "SWRB1207S-221MT"))
    )
    (comp (ref "L6")
      (value "220uH")
      (footprint "SRR1260")
      (description "L - INDUCTOR - 220uH - 1.6A - 12.5mm")
      (fields (field (name "LCSC PART #") "C169380") (field (name "Comment") "SWRB1207S-221MT"))
      (libsource (lib "JLC_PCB") (part "SWRB1207S-221MT"))
    )
    (comp (ref "L7")
      (value "220uH")
      (footprint "SRR1260")
      (description "L - INDUCTOR - 220uH - 1.6A - 12.5mm")
      (fields (field (name "LCSC PART #") "C169380") (field (name "Comment") "SWRB1207S-221MT"))
      (libsource (lib "JLC_PCB") (part "SWRB1207S-221MT"))
    )
    (comp (ref "L8")
      (value "220uH")
      (footprint "SRR1260")
      (description "L - INDUCTOR - 220uH - 1.6A - 12.5mm")
      (fields (field (name "LCSC PART #") "C169380") (field (name "Comment") "SWRB1207S-221MT"))
      (libsource (lib "JLC_PCB") (part "SWRB1207S-221MT"))
    )
    (comp (ref "L9")
      (value "220uH")
      (footprint "SRR1260")
      (description "L - INDUCTOR - 220uH - 1.6A - 12.5mm")
      (fields (field (name "LCSC PART #") "C169380") (field (name "Comment") "SWRB1207S-221MT"))
      (libsource (lib "JLC_PCB") (part "SWRB1207S-221MT"))
    )
    (comp (ref "L10")
      (value "220uH")
      (footprint "SRR1260")
      (description "L - INDUCTOR - 220uH - 1.6A - 12.5mm")
      (fields (field (name "LCSC PART #") "C169380") (field (name "Comment") "SWRB1207S-221MT"))
      (libsource (lib "JLC_PCB") (part "SWRB1207S-221MT"))
    )
    (comp (ref "L11")
      (value "220uH")
      (footprint "SRR1260")
      (description "L - INDUCTOR - 220uH - 1.6A - 12.5mm")
      (fields (field (name "LCSC PART #") "C169380") (field (name "Comment") "SWRB1207S-221MT"))
      (libsource (lib "JLC_PCB") (part "SWRB1207S-221MT"))
    )
    (comp (ref "L12")
      (value "220uH")
      (footprint "SRR1260")
      (description "L - INDUCTOR - 220uH - 1.6A - 12.5mm")
      (fields (field (name "LCSC PART #") "C169380") (field (name "Comment") "SWRB1207S-221MT"))
      (libsource (lib "JLC_PCB") (part "SWRB1207S-221MT"))
    )
    (comp (ref "NT2")
      (value "0")
      (footprint "NET_TIE")
      (description "R - Net Tie")
      (libsource (lib "JLC_PCB") (part "NET_TIE"))
    )
    (comp (ref "Q1")
      (value "IRF9540NSTRLPBF")
      (footprint "TO-263-3")
      (description "Q - TRANSISTOR - MOSFET (N) - 250V - 33A - 0.094R")
      (fields (field (name "LCSC PART #") "C33903"))
      (libsource (lib "JLC_PCB") (part "IRF9540NSTRLPBF"))
    )
    (comp (ref "Q2")
      (value "IRF9540NSTRLPBF")
      (footprint "TO-263-3")
      (description "Q - TRANSISTOR - MOSFET (N) - 250V - 33A - 0.094R")
      (fields (field (name "LCSC PART #") "C33903"))
      (libsource (lib "JLC_PCB") (part "IRF9540NSTRLPBF"))
    )
    (comp (ref "Q3")
      (value "IRF9540NSTRLPBF")
      (footprint "TO-263-3")
      (description "Q - TRANSISTOR - MOSFET (N) - 250V - 33A - 0.094R")
      (fields (field (name "LCSC PART #") "C33903"))
      (libsource (lib "JLC_PCB") (part "IRF9540NSTRLPBF"))
    )
    (comp (ref "Q4")
      (value "IRF9540NSTRLPBF")
      (footprint "TO-263-3")
      (description "Q - TRANSISTOR - MOSFET (N) - 250V - 33A - 0.094R")
      (fields (field (name "LCSC PART #") "C33903"))
      (libsource (lib "JLC_PCB") (part "IRF9540NSTRLPBF"))
    )
    (comp (ref "Q_I2C1")
      (value "2N7002")
      (footprint "TO-236AB")
      (description "Q - TRANSISTOR - MOSFET (N) - 60V - 200mW")
      (fields (field (name "LCSC PART #") "C8545"))
      (libsource (lib "JLC_PCB") (part "2N7002"))
    )
    (comp (ref "Q_I2C2")
      (value "2N7002")
      (footprint "TO-236AB")
      (description "Q - TRANSISTOR - MOSFET (N) - 60V - 200mW")
      (fields (field (name "LCSC PART #") "C8545"))
      (libsource (lib "JLC_PCB") (part "2N7002"))
    )
    (comp (ref "Q_LEDA")
      (value "2N7002")
      (footprint "TO-236AB")
      (description "Q - TRANSISTOR - MOSFET (N) - 60V - 200mW")
      (fields (field (name "LCSC PART #") "C8545"))
      (libsource (lib "JLC_PCB") (part "2N7002"))
    )
    (comp (ref "Q_LEDB")
      (value "2N7002")
      (footprint "TO-236AB")
      (description "Q - TRANSISTOR - MOSFET (N) - 60V - 200mW")
      (fields (field (name "LCSC PART #") "C8545"))
      (libsource (lib "JLC_PCB") (part "2N7002"))
    )
    (comp (ref "Q_LEDVSS")
      (value "2N7002")
      (footprint "TO-236AB")
      (description "Q - TRANSISTOR - MOSFET (N) - 60V - 200mW")
      (fields (field (name "LCSC PART #") "C8545"))
      (libsource (lib "JLC_PCB") (part "2N7002"))
    )
    (comp (ref "R1")
      (value "1m")
      (footprint "R_2512")
      (description "R - RESISTOR - SMD - 0.001R - 1% - 2512 - 2W - 50ppm/k")
      (fields (field (name "LCSC PART #") "C349153") (field (name "POWER") "2W"))
      (libsource (lib "JLC_PCB") (part "EWSL2512F1L00S9"))
    )
    (comp (ref "R3")
      (value "10k")
      (footprint "R_0402")
      (description "R - RESISTOR - SMD - 10k - 1% - 0402")
      (fields (field (name "LCSC PART #") "C25744") (field (name "Comment") "0402WGF1002TCE"))
      (libsource (lib "JLC_PCB") (part "0402WGF1002TCE"))
    )
    (comp (ref "R4")
      (value "10k")
      (footprint "R_0402")
      (description "R - RESISTOR - SMD - 10k - 1% - 0402")
      (fields (field (name "LCSC PART #") "C25744") (field (name "Comment") "0402WGF1002TCE"))
      (libsource (lib "JLC_PCB") (part "0402WGF1002TCE"))
    )
    (comp (ref "R5")
      (value "33k")
      (footprint "R_0402")
      (description "R - RESISTOR - SMD - 33k - 1% - 0402")
      (fields (field (name "LCSC PART #") "C25779") (field (name "Comment") "0402WGF3302TCE"))
      (libsource (lib "JLC_PCB") (part "0402WGF3302TCE"))
    )
    (comp (ref "R5_a")
      (value "100k")
      (footprint "R_0402")
      (description "R - RESISTOR - SMD - 100k - 1% -  0402")
      (fields (field (name "LCSC PART #") "C25741") (field (name "Comment") "0402WGF1003TCE"))
      (libsource (lib "JLC_PCB") (part "0402WGF1003TCE"))
    )
    (comp (ref "R8")
      (value "220R")
      (footprint "R_0402")
      (description "R - RESISTOR - SMD - 220R - 1% - 0402")
      (fields (field (name "LCSC PART #") "C25091") (field (name "Comment") "0402WGF2200TCE"))
      (libsource (lib "JLC_PCB") (part "0402WGF2200TCE"))
    )
    (comp (ref "R8_A")
      (value "220R")
      (footprint "R_0402")
      (description "R - RESISTOR - SMD - 220R - 1% - 0402")
      (fields (field (name "LCSC PART #") "C25091"))
      (libsource (lib "*") (part "0402WGF2200TCE"))
    )
    (comp (ref "R9")
      (value "10k")
      (footprint "R_0402")
      (description "R - RESISTOR - SMD - 10k - 1% - 0402")
      (fields (field (name "LCSC PART #") "C25744") (field (name "Comment") "0402WGF1002TCE"))
      (libsource (lib "JLC_PCB") (part "0402WGF1002TCE"))
    )
    (comp (ref "R10")
      (value "1m")
      (footprint "R_2512")
      (description "R - RESISTOR - SMD - 0.001R - 1% - 2512 - 2W - 50ppm/k")
      (fields (field (name "LCSC PART #") "C349153") (field (name "POWER") "2W"))
      (libsource (lib "JLC_PCB") (part "EWSL2512F1L00S9"))
    )
    (comp (ref "R11")
      (value "10R")
      (footprint "R_1206")
      (description "R - RESISTOR - SMD - 10R - 1% - 1206")
      (fields (field (name "LCSC PART #") "C17903") (field (name "Comment") "1206W4F100JT5E"))
      (libsource (lib "JLC_PCB") (part "1206W4F100JT5E"))
    )
    (comp (ref "R12")
      (value "220R")
      (footprint "R_0402")
      (description "R - RESISTOR - SMD - 220R - 1% - 0402")
      (fields (field (name "LCSC PART #") "C25091") (field (name "Comment") "0402WGF2200TCE"))
      (libsource (lib "JLC_PCB") (part "0402WGF2200TCE"))
    )
    (comp (ref "R12_A")
      (value "220R")
      (footprint "R_0402")
      (description "R - RESISTOR - SMD - 220R - 1% - 0402")
      (fields (field (name "LCSC PART #") "C25091") (field (name "Comment") "0402WGF2200TCE"))
      (libsource (lib "JLC_PCB") (part "0402WGF2200TCE"))
    )
    (comp (ref "R13")
      (value "100k")
      (footprint "R_0603")
      (description "R - RESISTOR - SMD - 100k - 1% -  0603")
      (fields (field (name "LCSC PART #") "C22936") (field (name "Comment") "0603WAF100KT5E"))
      (libsource (lib "JLC_PCB") (part "0603WAF100KT5E"))
    )
    (comp (ref "R14")
      (value "10R")
      (footprint "R_1206")
      (description "R - RESISTOR - SMD - 10R - 1% - 1206")
      (fields (field (name "LCSC PART #") "C17903") (field (name "Comment") "1206W4F100JT5E"))
      (libsource (lib "JLC_PCB") (part "1206W4F100JT5E"))
    )
    (comp (ref "R15")
      (value "3.3k")
      (footprint "R_0402")
      (description "R - RESISTOR - SMD - 3.3k - 1% - 0402")
      (fields (field (name "LCSC PART #") "C25890") (field (name "Comment") "0402WGF3301TCE"))
      (libsource (lib "JLC_PCB") (part "0402WGF3301TCE"))
    )
    (comp (ref "R16")
      (value "0R")
      (footprint "R_0402")
      (description "R - RESISTOR - SMD - 0R - 1% - 0402")
      (fields (field (name "LCSC PART #") "C17168") (field (name "Comment") "0402WGF0000TCE"))
      (libsource (lib "JLC_PCB") (part "0402WGF0000TCE"))
    )
    (comp (ref "R17")
      (value "0R")
      (footprint "R_0402")
      (description "R - RESISTOR - SMD - 0R - 1% - 0402")
      (fields (field (name "LCSC PART #") "C17168") (field (name "Comment") "0402WGF0000TCE"))
      (libsource (lib "JLC_PCB") (part "0402WGF0000TCE"))
    )
    (comp (ref "R18")
      (value "10R")
      (footprint "R_0402")
      (description "R - RESISTOR - SMD - 10R - 1% - 0402")
      (fields (field (name "LCSC PART #") "C25077") (field (name "Comment") "0402WGF100JTCE"))
      (libsource (lib "JLC_PCB") (part "0402WGF100JTCE"))
    )
    (comp (ref "R18_a")
      (value "10R")
      (footprint "R_0402")
      (description "R - RESISTOR - SMD - 10R - 1% - 0402")
      (fields (field (name "LCSC PART #") "C25077") (field (name "Comment") "0402WGF100JTCE"))
      (libsource (lib "JLC_PCB") (part "0402WGF100JTCE"))
    )
    (comp (ref "R19")
      (value "10R")
      (footprint "R_0402")
      (description "R - RESISTOR - SMD - 10R - 1% - 0402")
      (fields (field (name "LCSC PART #") "C25077") (field (name "Comment") "0402WGF100JTCE"))
      (libsource (lib "JLC_PCB") (part "0402WGF100JTCE"))
    )
    (comp (ref "R19_a")
      (value "10R")
      (footprint "R_0402")
      (description "R - RESISTOR - SMD - 10R - 1% - 0402")
      (fields (field (name "LCSC PART #") "C25077") (field (name "Comment") "0402WGF100JTCE"))
      (libsource (lib "JLC_PCB") (part "0402WGF100JTCE"))
    )
    (comp (ref "R20")
      (value "4.7k")
      (footprint "R_0402")
      (description "R - RESISTOR - SMD - 4.7k - 1% - 0402")
      (fields (field (name "LCSC PART #") "C25900") (field (name "Comment") "0402WGF4701TCE"))
      (libsource (lib "JLC_PCB") (part "0402WGF4701TCE"))
    )
    (comp (ref "R21")
      (value "10R")
      (footprint "R_0402")
      (description "R - RESISTOR - SMD - 10R - 1% - 0402")
      (fields (field (name "LCSC PART #") "C25077") (field (name "Comment") "0402WGF100JTCE"))
      (libsource (lib "JLC_PCB") (part "0402WGF100JTCE"))
    )
    (comp (ref "R22")
      (value "10k")
      (footprint "R_0402")
      (description "R - RESISTOR - SMD - 10k - 1% - 0402")
      (fields (field (name "LCSC PART #") "C25744") (field (name "Comment") "0402WGF1002TCE"))
      (libsource (lib "JLC_PCB") (part "0402WGF1002TCE"))
    )
    (comp (ref "R23")
      (value "10k")
      (footprint "R_0402")
      (description "R - RESISTOR - SMD - 10k - 1% - 0402")
      (fields (field (name "LCSC PART #") "C25744") (field (name "Comment") "0402WGF1002TCE"))
      (libsource (lib "JLC_PCB") (part "0402WGF1002TCE"))
    )
    (comp (ref "R24")
      (value "220R")
      (footprint "R_0402")
      (description "R - RESISTOR - SMD - 220R - 1% - 0402")
      (fields (field (name "LCSC PART #") "C25091") (field (name "Comment") "0402WGF2200TCE"))
      (libsource (lib "JLC_PCB") (part "0402WGF2200TCE"))
    )
    (comp (ref "R24_A")
      (value "220R")
      (footprint "R_0402")
      (description "R - RESISTOR - SMD - 220R - 1% - 0402")
      (fields (field (name "LCSC PART #") "C25091") (field (name "Comment") "0402WGF2200TCE"))
      (libsource (lib "JLC_PCB") (part "0402WGF2200TCE"))
    )
    (comp (ref "R24_B")
      (value "220R")
      (footprint "R_0402")
      (description "R - RESISTOR - SMD - 220R - 1% - 0402")
      (fields (field (name "LCSC PART #") "C25091") (field (name "Comment") "0402WGF2200TCE"))
      (libsource (lib "JLC_PCB") (part "0402WGF2200TCE"))
    )
    (comp (ref "R25")
      (value "0R")
      (footprint "R_0402")
      (description "R - RESISTOR - SMD - 0R - 1% - 0402")
      (fields (field (name "LCSC PART #") "C17168") (field (name "Comment") "0402WGF0000TCE"))
      (libsource (lib "JLC_PCB") (part "0402WGF0000TCE"))
    )
    (comp (ref "R26")
      (value "10k")
      (footprint "R_0402")
      (description "R - RESISTOR - SMD - 10k - 1% - 0402")
      (fields (field (name "LCSC PART #") "C25744") (field (name "Comment") "0402WGF1002TCE"))
      (libsource (lib "JLC_PCB") (part "0402WGF1002TCE"))
    )
    (comp (ref "R28")
      (value "33k")
      (footprint "R_0402")
      (description "R - RESISTOR - SMD - 33k - 1% - 0402")
      (fields (field (name "LCSC PART #") "C25779") (field (name "Comment") "0402WGF3302TCE"))
      (libsource (lib "JLC_PCB") (part "0402WGF3302TCE"))
    )
    (comp (ref "R29")
      (value "0R")
      (footprint "R_0402")
      (description "R - RESISTOR - SMD - 0R - 1% - 0402")
      (fields (field (name "LCSC PART #") "C17168") (field (name "Comment") "0402WGF0000TCE"))
      (libsource (lib "JLC_PCB") (part "0402WGF0000TCE"))
    )
    (comp (ref "R30")
      (value "0R")
      (footprint "R_0402")
      (description "R - RESISTOR - SMD - 0R - 1% - 0402")
      (fields (field (name "LCSC PART #") "C17168") (field (name "Comment") "0402WGF0000TCE"))
      (libsource (lib "JLC_PCB") (part "0402WGF0000TCE"))
    )
    (comp (ref "R31")
      (value "0R")
      (footprint "R_0402")
      (description "R - RESISTOR - SMD - 0R - 1% - 0402")
      (fields (field (name "LCSC PART #") "C17168") (field (name "Comment") "0402WGF0000TCE"))
      (libsource (lib "JLC_PCB") (part "0402WGF0000TCE"))
    )
    (comp (ref "R32")
      (value "10R")
      (footprint "R_0402")
      (description "R - RESISTOR - SMD - 10R - 1% - 0402")
      (fields (field (name "LCSC PART #") "C25077") (field (name "Comment") "0402WGF100JTCE"))
      (libsource (lib "JLC_PCB") (part "0402WGF100JTCE"))
    )
    (comp (ref "R32_a")
      (value "10R")
      (footprint "R_0402")
      (description "R - RESISTOR - SMD - 10R - 1% - 0402")
      (fields (field (name "LCSC PART #") "C25077") (field (name "Comment") "0402WGF100JTCE"))
      (libsource (lib "JLC_PCB") (part "0402WGF100JTCE"))
    )
    (comp (ref "R33")
      (value "10R")
      (footprint "R_0402")
      (description "R - RESISTOR - SMD - 10R - 1% - 0402")
      (fields (field (name "LCSC PART #") "C25077") (field (name "Comment") "0402WGF100JTCE"))
      (libsource (lib "JLC_PCB") (part "0402WGF100JTCE"))
    )
    (comp (ref "R33_a")
      (value "10R")
      (footprint "R_0402")
      (description "R - RESISTOR - SMD - 10R - 1% - 0402")
      (fields (field (name "LCSC PART #") "C25077") (field (name "Comment") "0402WGF100JTCE"))
      (libsource (lib "JLC_PCB") (part "0402WGF100JTCE"))
    )
    (comp (ref "R34")
      (value "220R")
      (footprint "R_0402")
      (description "R - RESISTOR - SMD - 220R - 1% - 0402")
      (fields (field (name "LCSC PART #") "C25091") (field (name "Comment") "0402WGF2200TCE"))
      (libsource (lib "JLC_PCB") (part "0402WGF2200TCE"))
    )
    (comp (ref "R35")
      (value "0R")
      (footprint "R_0402")
      (description "R - RESISTOR - SMD - 0R - 1% - 0402")
      (fields (field (name "LCSC PART #") "C17168") (field (name "Comment") "0402WGF0000TCE"))
      (libsource (lib "JLC_PCB") (part "0402WGF0000TCE"))
    )
    (comp (ref "R36")
      (value "10k")
      (footprint "R_0402")
      (description "R - RESISTOR - SMD - 10k - 1% - 0402")
      (fields (field (name "LCSC PART #") "C25744") (field (name "Comment") "0402WGF1002TCE"))
      (libsource (lib "JLC_PCB") (part "0402WGF1002TCE"))
    )
    (comp (ref "R37")
      (value "0R")
      (footprint "R_0402")
      (description "R - RESISTOR - SMD - 0R - 1% - 0402")
      (fields (field (name "LCSC PART #") "C17168") (field (name "Comment") "0402WGF0000TCE"))
      (libsource (lib "JLC_PCB") (part "0402WGF0000TCE"))
    )
    (comp (ref "R38")
      (value "4.7k")
      (footprint "R_0402")
      (description "R - RESISTOR - SMD - 4.7k - 1% - 0402")
      (fields (field (name "LCSC PART #") "C25900") (field (name "Comment") "0402WGF4701TCE"))
      (libsource (lib "JLC_PCB") (part "0402WGF4701TCE"))
    )
    (comp (ref "R39")
      (value "1M")
      (footprint "R_0402")
      (description "R - RESISTOR - SMD - 1M - 1% - 0402")
      (fields (field (name "LCSC PART #") "C26083") (field (name "Comment") "0402WGF1004TCE"))
      (libsource (lib "JLC_PCB") (part "0402WGF1004TCE"))
    )
    (comp (ref "R40")
      (value "1M")
      (footprint "R_0402")
      (description "R - RESISTOR - SMD - 1M - 1% - 0402")
      (fields (field (name "LCSC PART #") "C26083") (field (name "Comment") "0402WGF1004TCE"))
      (libsource (lib "JLC_PCB") (part "0402WGF1004TCE"))
    )
    (comp (ref "R41")
      (value "100k")
      (footprint "R_0402")
      (description "R - RESISTOR - SMD - 100k - 1% -  0402")
      (fields (field (name "LCSC PART #") "C25741") (field (name "Comment") "0402WGF1003TCE"))
      (libsource (lib "JLC_PCB") (part "0402WGF1003TCE"))
    )
    (comp (ref "R42")
      (value "10k")
      (footprint "R_0402")
      (description "R - RESISTOR - SMD - 10k - 1% - 0402")
      (fields (field (name "LCSC PART #") "C25744") (field (name "Comment") "0402WGF1002TCE"))
      (libsource (lib "JLC_PCB") (part "0402WGF1002TCE"))
    )
    (comp (ref "R43")
      (value "10k")
      (footprint "R_0402")
      (description "R - RESISTOR - SMD - 10k - 1% - 0402")
      (fields (field (name "LCSC PART #") "C25744") (field (name "Comment") "0402WGF1002TCE"))
      (libsource (lib "JLC_PCB") (part "0402WGF1002TCE"))
    )
    (comp (ref "R44")
      (value "0R")
      (footprint "R_0402")
      (description "R - RESISTOR - SMD - 0R - 1% - 0402")
      (fields (field (name "LCSC PART #") "C17168") (field (name "Comment") "0402WGF0000TCE"))
      (libsource (lib "JLC_PCB") (part "0402WGF0000TCE"))
    )
    (comp (ref "R45")
      (value "10k")
      (footprint "R_0402")
      (description "R - RESISTOR - SMD - 10k - 1% - 0402")
      (fields (field (name "LCSC PART #") "C25744") (field (name "Comment") "0402WGF1002TCE"))
      (libsource (lib "JLC_PCB") (part "0402WGF1002TCE"))
    )
    (comp (ref "R47")
      (value "10k")
      (footprint "R_0402")
      (description "R - RESISTOR - SMD - 10k - 1% - 0402")
      (fields (field (name "LCSC PART #") "C25744") (field (name "Comment") "0402WGF1002TCE"))
      (libsource (lib "JLC_PCB") (part "0402WGF1002TCE"))
    )
    (comp (ref "R48")
      (value "10k")
      (footprint "R_0402")
      (description "R - RESISTOR - SMD - 10k - 1% - 0402")
      (fields (field (name "LCSC PART #") "C25744") (field (name "Comment") "0402WGF1002TCE"))
      (libsource (lib "JLC_PCB") (part "0402WGF1002TCE"))
    )
    (comp (ref "R51")
      (value "100k")
      (footprint "R_0603")
      (description "R - RESISTOR - SMD - 100k - 1% -  0603")
      (fields (field (name "LCSC PART #") "C22936") (field (name "Comment") "0603WAF100KT5E"))
      (libsource (lib "JLC_PCB") (part "0603WAF100KT5E"))
    )
    (comp (ref "R53")
      (value "4.7k")
      (footprint "R_0402")
      (description "R - RESISTOR - SMD - 4.7k - 1% - 0402")
      (fields (field (name "LCSC PART #") "C25900") (field (name "Comment") "0402WGF4701TCE"))
      (libsource (lib "JLC_PCB") (part "0402WGF4701TCE"))
    )
    (comp (ref "R56")
      (value "47k")
      (footprint "R_0402")
      (description "R - RESISTOR - SMD - 47k - 1% - 0402")
      (fields (field (name "LCSC PART #") "C25792") (field (name "Comment") "0402WGF4702TCE"))
      (libsource (lib "JLC_PCB") (part "0402WGF4702TCE"))
    )
    (comp (ref "R87_a")
      (value "47k")
      (footprint "R_0402")
      (description "R - RESISTOR - SMD - 47k - 1% - 0402")
      (fields (field (name "LCSC PART #") "C25792") (field (name "Comment") "0402WGF4702TCE"))
      (libsource (lib "JLC_PCB") (part "0402WGF4702TCE"))
    )
    (comp (ref "R100")
      (value "1k")
      (footprint "R_0402")
      (description "R - RESISTOR - SMD - 1k - 1% - 0402")
      (fields (field (name "LCSC PART #") "C11702") (field (name "Comment") "0402WGF1001TCE"))
      (libsource (lib "JLC_PCB") (part "0402WGF1001TCE"))
    )
    (comp (ref "R101")
      (value "1k")
      (footprint "R_0402")
      (description "R - RESISTOR - SMD - 1k - 1% - 0402")
      (fields (field (name "LCSC PART #") "C11702") (field (name "Comment") "0402WGF1001TCE"))
      (libsource (lib "JLC_PCB") (part "0402WGF1001TCE"))
    )
    (comp (ref "R102")
      (value "1k")
      (footprint "R_0402")
      (description "R - RESISTOR - SMD - 1k - 1% - 0402")
      (fields (field (name "LCSC PART #") "C11702") (field (name "Comment") "0402WGF1001TCE"))
      (libsource (lib "JLC_PCB") (part "0402WGF1001TCE"))
    )
    (comp (ref "R103")
      (value "1k")
      (footprint "R_0402")
      (description "R - RESISTOR - SMD - 1k - 1% - 0402")
      (fields (field (name "LCSC PART #") "C11702") (field (name "Comment") "0402WGF1001TCE"))
      (libsource (lib "JLC_PCB") (part "0402WGF1001TCE"))
    )
    (comp (ref "R116")
      (value "47k")
      (footprint "R_0402")
      (description "R - RESISTOR - SMD - 47k - 1% - 0402")
      (fields (field (name "LCSC PART #") "C25792") (field (name "Comment") "0402WGF4702TCE"))
      (libsource (lib "JLC_PCB") (part "0402WGF4702TCE"))
    )
    (comp (ref "R121")
      (value "10k")
      (footprint "R_0402")
      (description "R - RESISTOR - SMD - 10k - 1% - 0402")
      (fields (field (name "LCSC PART #") "C25744") (field (name "Comment") "0402WGF1002TCE"))
      (libsource (lib "JLC_PCB") (part "0402WGF1002TCE"))
    )
    (comp (ref "RA1_N")
      (value "0R")
      (footprint "R_0402")
      (description "R - RESISTOR - SMD - 0R - 1% - 0402")
      (fields (field (name "LCSC PART #") "C17168") (field (name "Comment") "0402WGF0000TCE"))
      (libsource (lib "JLC_PCB") (part "0402WGF0000TCE"))
    )
    (comp (ref "RA1_P")
      (value "0R")
      (footprint "R_0402")
      (description "R - RESISTOR - SMD - 0R - 1% - 0402")
      (fields (field (name "LCSC PART #") "C17168") (field (name "Comment") "0402WGF0000TCE"))
      (libsource (lib "JLC_PCB") (part "0402WGF0000TCE"))
    )
    (comp (ref "RB1_N")
      (value "0R")
      (footprint "R_0402")
      (description "R - RESISTOR - SMD - 0R - 1% - 0402")
      (fields (field (name "LCSC PART #") "C17168") (field (name "Comment") "0402WGF0000TCE"))
      (libsource (lib "JLC_PCB") (part "0402WGF0000TCE"))
    )
    (comp (ref "RB1_P")
      (value "0R")
      (footprint "R_0402")
      (description "R - RESISTOR - SMD - 0R - 1% - 0402")
      (fields (field (name "LCSC PART #") "C17168") (field (name "Comment") "0402WGF0000TCE"))
      (libsource (lib "JLC_PCB") (part "0402WGF0000TCE"))
    )
    (comp (ref "Ron_a")
      (value "100k")
      (footprint "R_0402")
      (description "R - RESISTOR - SMD - 100k - 1% -  0402")
      (fields (field (name "LCSC PART #") "C25741") (field (name "Comment") "0402WGF1003TCE"))
      (libsource (lib "JLC_PCB") (part "0402WGF1003TCE"))
    )
    (comp (ref "Ron_b")
      (value "100k")
      (footprint "R_0402")
      (description "R - RESISTOR - SMD - 100k - 1% -  0402")
      (fields (field (name "LCSC PART #") "C25741") (field (name "Comment") "0402WGF1003TCE"))
      (libsource (lib "JLC_PCB") (part "0402WGF1003TCE"))
    )
    (comp (ref "Ron_c")
      (value "100k")
      (footprint "R_0402")
      (description "R - RESISTOR - SMD - 100k - 1% -  0402")
      (fields (field (name "LCSC PART #") "C25741") (field (name "Comment") "0402WGF1003TCE"))
      (libsource (lib "JLC_PCB") (part "0402WGF1003TCE"))
    )
    (comp (ref "Ron_d")
      (value "100k")
      (footprint "R_0402")
      (description "R - RESISTOR - SMD - 100k - 1% -  0402")
      (fields (field (name "LCSC PART #") "C25741") (field (name "Comment") "0402WGF1003TCE"))
      (libsource (lib "JLC_PCB") (part "0402WGF1003TCE"))
    )
    (comp (ref "R_1A_a")
      (value "47k")
      (footprint "R_0402")
      (description "R - RESISTOR - SMD - 47k - 1% - 0402")
      (fields (field (name "LCSC PART #") "C25792") (field (name "Comment") "0402WGF4702TCE"))
      (libsource (lib "JLC_PCB") (part "0402WGF4702TCE"))
    )
    (comp (ref "R_1A_b")
      (value "47k")
      (footprint "R_0402")
      (description "R - RESISTOR - SMD - 47k - 1% - 0402")
      (fields (field (name "LCSC PART #") "C25792") (field (name "Comment") "0402WGF4702TCE"))
      (libsource (lib "JLC_PCB") (part "0402WGF4702TCE"))
    )
    (comp (ref "R_1A_c")
      (value "100k")
      (footprint "R_0402")
      (description "R - RESISTOR - SMD - 100k - 1% -  0402")
      (fields (field (name "LCSC PART #") "C25741") (field (name "Comment") "0402WGF1003TCE"))
      (libsource (lib "JLC_PCB") (part "0402WGF1003TCE"))
    )
    (comp (ref "R_1B_a")
      (value "47k")
      (footprint "R_0402")
      (description "R - RESISTOR - SMD - 47k - 1% - 0402")
      (fields (field (name "LCSC PART #") "C25792") (field (name "Comment") "0402WGF4702TCE"))
      (libsource (lib "JLC_PCB") (part "0402WGF4702TCE"))
    )
    (comp (ref "R_1B_b")
      (value "47k")
      (footprint "R_0402")
      (description "R - RESISTOR - SMD - 47k - 1% - 0402")
      (fields (field (name "LCSC PART #") "C25792") (field (name "Comment") "0402WGF4702TCE"))
      (libsource (lib "JLC_PCB") (part "0402WGF4702TCE"))
    )
    (comp (ref "R_1B_c")
      (value "100k")
      (footprint "R_0402")
      (description "R - RESISTOR - SMD - 100k - 1% -  0402")
      (fields (field (name "LCSC PART #") "C25741") (field (name "Comment") "0402WGF1003TCE"))
      (libsource (lib "JLC_PCB") (part "0402WGF1003TCE"))
    )
    (comp (ref "R_LEDA_O")
      (value "0R")
      (footprint "R_0402")
      (description "R - RESISTOR - SMD - 0R - 1% - 0402")
      (fields (field (name "LCSC PART #") "C17168") (field (name "Comment") "0402WGF0000TCE"))
      (libsource (lib "JLC_PCB") (part "0402WGF0000TCE"))
    )
    (comp (ref "R_LEDB_O")
      (value "0R")
      (footprint "R_0402")
      (description "R - RESISTOR - SMD - 0R - 1% - 0402")
      (fields (field (name "LCSC PART #") "C17168") (field (name "Comment") "0402WGF0000TCE"))
      (libsource (lib "JLC_PCB") (part "0402WGF0000TCE"))
    )
    (comp (ref "R_SCL3")
      (value "10k")
      (footprint "R_0402")
      (description "R - RESISTOR - SMD - 10k - 1% - 0402")
      (fields (field (name "LCSC PART #") "C25744") (field (name "Comment") "0402WGF1002TCE"))
      (libsource (lib "JLC_PCB") (part "0402WGF1002TCE"))
    )
    (comp (ref "R_SDA3")
      (value "10k")
      (footprint "R_0402")
      (description "R - RESISTOR - SMD - 10k - 1% - 0402")
      (fields (field (name "LCSC PART #") "C25744") (field (name "Comment") "0402WGF1002TCE"))
      (libsource (lib "JLC_PCB") (part "0402WGF1002TCE"))
    )
    (comp (ref "U1")
      (value "LM5008MMX/NOPB")
      (footprint "SOP65P490X110-8N")
      (description "U - IC - BUCK CONVERTER, ADJUSTABLE, 95V, 350mA")
      (libsource (lib "JLC_PCB") (part "LM5008MMX/NOPB"))
    )
    (comp (ref "U5V")
      (value "L78M05ABDT-TR")
      (footprint "TO-252AA")
      (description "U - IC - 5V Power Regulator")
      (fields (field (name "LCSC PART #") "C58069"))
      (libsource (lib "JLC_PCB") (part "L78M05ABDT-TR"))
    )
    (comp (ref "U7")
      (value "SM72295MAX")
      (footprint "M28B_M")
      (description "Photovoltaic Full Bridge Driver")
      (fields (field (name "MANUFACTURER") "National Semiconductor") (field (name "PARTNUMBER") "SM72295"))
      (libsource (lib "SM_ICs") (part "SM72295"))
    )
    (comp (ref "U8")
      (value "SM72442MTE/NOPB")
      (footprint "MTC28_L")
      (description "Programmable Maximum Power Point Tracking Controller for Photovoltaic Solar Panels")
      (fields (field (name "MANUFACTURER") "National Semiconductor") (field (name "PARTNUMBER") "SM72442"))
      (libsource (lib "SM_ICs") (part "SM72442"))
    )
  )
  (nets
    (net (code "1") (name "+5VDC") (class "Default")
      (node (ref "C32") (pin "2") (pinfunction "2_2") (pintype "passive"))
      (node (ref "C34") (pin "2") (pinfunction "2_2") (pintype "passive"))
      (node (ref "C37") (pin "1") (pinfunction "1_1") (pintype "passive"))
      (node (ref "C38") (pin "2") (pinfunction "2_2") (pintype "passive"))
      (node (ref "C42") (pin "2") (pinfunction "2_2") (pintype "passive"))
      (node (ref "R100") (pin "1") (pinfunction "1_1") (pintype "passive"))
      (node (ref "R101") (pin "1") (pinfunction "1_1") (pintype "passive"))
      (node (ref "R102") (pin "1") (pinfunction "1_1") (pintype "passive"))
      (node (ref "R103") (pin "1") (pinfunction "1_1") (pintype "passive"))
      (node (ref "R17") (pin "2") (pinfunction "2_2") (pintype "passive"))
      (node (ref "R21") (pin "2") (pinfunction "2_2") (pintype "passive"))
      (node (ref "R26") (pin "2") (pinfunction "2_2") (pintype "passive"))
      (node (ref "R28") (pin "2") (pinfunction "2_2") (pintype "passive"))
      (node (ref "R29") (pin "2") (pinfunction "2_2") (pintype "passive"))
      (node (ref "R30") (pin "1") (pinfunction "1_1") (pintype "passive"))
      (node (ref "R31") (pin "2") (pinfunction "2_2") (pintype "passive"))
      (node (ref "R36") (pin "1") (pinfunction "1_1") (pintype "passive"))
      (node (ref "R45") (pin "1") (pinfunction "1_1") (pintype "passive"))
      (node (ref "R47") (pin "2") (pinfunction "2_2") (pintype "passive"))
      (node (ref "R48") (pin "2") (pinfunction "2_2") (pintype "passive"))
      (node (ref "R87_a") (pin "2") (pinfunction "2_2") (pintype "passive"))
      (node (ref "U7") (pin "17") (pinfunction "VDD_17") (pintype "power_in"))
      (node (ref "U8") (pin "3") (pinfunction "VDDD_3") (pintype "power_in"))
    )
    (net (code "2") (name "/1A_GATE") (class "Default")
      (node (ref "D_1A") (pin "2") (pinfunction "A_2") (pintype "passive"))
      (node (ref "D_1A_G") (pin "1") (pinfunction "K_1") (pintype "passive"))
      (node (ref "Q_LEDA") (pin "1") (pinfunction "G_1") (pintype "passive"))
      (node (ref "R_1A_b") (pin "2") (pinfunction "2_2") (pintype "passive"))
      (node (ref "R_1A_c") (pin "2") (pinfunction "2_2") (pintype "passive"))
    )
    (net (code "3") (name "/1B_GATE") (class "Default")
      (node (ref "D_1B") (pin "2") (pinfunction "A_2") (pintype "passive"))
      (node (ref "D_1B_G") (pin "1") (pinfunction "K_1") (pintype "passive"))
      (node (ref "R_1B_b") (pin "2") (pinfunction "2_2") (pintype "passive"))
      (node (ref "R_1B_c") (pin "2") (pinfunction "2_2") (pintype "passive"))
    )
    (net (code "4") (name "/3V3_SCL") (class "Default")
      (node (ref "Q_I2C1") (pin "2") (pinfunction "S_2") (pintype "passive"))
      (node (ref "R_SCL3") (pin "1") (pinfunction "1_1") (pintype "passive"))
    )
    (net (code "5") (name "/3V3_SDA") (class "Default")
      (node (ref "Q_I2C2") (pin "2") (pinfunction "S_2") (pintype "passive"))
      (node (ref "R_SDA3") (pin "1") (pinfunction "1_1") (pintype "passive"))
    )
    (net (code "6") (name "/5V_SCL") (class "Default")
      (node (ref "Q_I2C1") (pin "3") (pinfunction "D_3") (pintype "passive"))
      (node (ref "R48") (pin "1") (pinfunction "1_1") (pintype "passive"))
      (node (ref "U8") (pin "8") (pinfunction "SCL_8") (pintype "input"))
    )
    (net (code "7") (name "/5V_SDA") (class "Default")
      (node (ref "Q_I2C2") (pin "3") (pinfunction "D_3") (pintype "passive"))
      (node (ref "R47") (pin "1") (pinfunction "1_1") (pintype "passive"))
      (node (ref "U8") (pin "9") (pinfunction "SDA_9") (pintype "bidirectional"))
    )
    (net (code "8") (name "/A1_N") (class "Default")
      (node (ref "R12") (pin "1") (pinfunction "1_1") (pintype "passive"))
      (node (ref "RA1_P") (pin "2") (pinfunction "2_2") (pintype "passive"))
    )
    (net (code "9") (name "/A1_P") (class "Default")
      (node (ref "R8") (pin "1") (pinfunction "1_1") (pintype "passive"))
      (node (ref "RA1_N") (pin "2") (pinfunction "2_2") (pintype "passive"))
    )
    (net (code "10") (name "/A2_N") (class "Default")
      (node (ref "R24_A") (pin "2") (pinfunction "2_2") (pintype "passive"))
      (node (ref "RB1_N") (pin "2") (pinfunction "2_2") (pintype "passive"))
    )
    (net (code "11") (name "/A2_P") (class "Default")
      (node (ref "R24_B") (pin "2") (pinfunction "2_2") (pintype "passive"))
      (node (ref "RB1_P") (pin "2") (pinfunction "2_2") (pintype "passive"))
    )
    (net (code "12") (name "/AIIN") (class "Default")
      (node (ref "C58") (pin "2") (pinfunction "2_2") (pintype "passive"))
      (node (ref "R44") (pin "1") (pinfunction "1_1") (pintype "passive"))
      (node (ref "U8") (pin "19") (pinfunction "AIIN_19") (pintype "input"))
    )
    (net (code "13") (name "/AIOUT") (class "Default")
      (node (ref "C60") (pin "2") (pinfunction "2_2") (pintype "passive"))
      (node (ref "R37") (pin "1") (pinfunction "1_1") (pintype "passive"))
      (node (ref "U8") (pin "21") (pinfunction "AIOUT_21") (pintype "output"))
    )
    (net (code "14") (name "/AVIN") (class "Default")
      (node (ref "C29") (pin "2") (pinfunction "2_2") (pintype "passive"))
      (node (ref "R13") (pin "1") (pinfunction "1_1") (pintype "passive"))
      (node (ref "R20") (pin "1") (pinfunction "1_1") (pintype "passive"))
      (node (ref "U8") (pin "15") (pinfunction "AVIN_15") (pintype "input"))
    )
    (net (code "15") (name "/AVOUT") (class "Default")
      (node (ref "C59") (pin "2") (pinfunction "2_2") (pintype "passive"))
      (node (ref "R51") (pin "1") (pinfunction "1_1") (pintype "passive"))
      (node (ref "R53") (pin "1") (pinfunction "1_1") (pintype "passive"))
      (node (ref "U8") (pin "17") (pinfunction "AVOUT_17") (pintype "output"))
    )
    (net (code "16") (name "/BIN") (class "Default")
      (node (ref "R37") (pin "2") (pinfunction "2_2") (pintype "passive"))
      (node (ref "U7") (pin "4") (pinfunction "BIN_4") (pintype "output"))
    )
    (net (code "17") (name "/BOUT") (class "Default")
      (node (ref "R44") (pin "2") (pinfunction "2_2") (pintype "passive"))
      (node (ref "U7") (pin "11") (pinfunction "BOUT_11") (pintype "output"))
    )
    (net (code "18") (name "/GND_OUT") (class "Default")
      (node (ref "J_OUT") (pin "MINUS") (pinfunction "-_MINUS") (pintype "passive"))
    )
    (net (code "19") (name "/HIA") (class "Default")
      (node (ref "U7") (pin "7") (pinfunction "HIA_7") (pintype "input"))
      (node (ref "U8") (pin "26") (pinfunction "HIA_26") (pintype "output"))
    )
    (net (code "20") (name "/HIB") (class "Default")
      (node (ref "U7") (pin "8") (pinfunction "HIB_8") (pintype "input"))
      (node (ref "U8") (pin "25") (pinfunction "HIB_25") (pintype "output"))
    )
    (net (code "21") (name "/HO_A") (class "Default")
      (node (ref "D3") (pin "1") (pinfunction "K_1") (pintype "passive"))
      (node (ref "R18") (pin "1") (pinfunction "1_1") (pintype "passive"))
      (node (ref "R18_a") (pin "1") (pinfunction "1_1") (pintype "passive"))
      (node (ref "U7") (pin "27") (pinfunction "HOA_27") (pintype "output"))
    )
    (net (code "22") (name "/HO_B") (class "Default")
      (node (ref "D4") (pin "1") (pinfunction "K_1") (pintype "passive"))
      (node (ref "R19") (pin "2") (pinfunction "2_2") (pintype "passive"))
      (node (ref "R19_a") (pin "2") (pinfunction "2_2") (pintype "passive"))
      (node (ref "U7") (pin "19") (pinfunction "HOB_19") (pintype "output"))
    )
    (net (code "23") (name "/HS_A") (class "Default")
      (node (ref "C18") (pin "2") (pinfunction "2_2") (pintype "passive"))
      (node (ref "C46") (pin "2") (pinfunction "2_2") (pintype "passive"))
      (node (ref "D12") (pin "1") (pinfunction "K_1") (pintype "passive"))
      (node (ref "D13") (pin "2") (pinfunction "A_2") (pintype "passive"))
      (node (ref "L1") (pin "1") (pinfunction "1_1") (pintype "passive"))
      (node (ref "L10") (pin "1") (pinfunction "1_1") (pintype "passive"))
      (node (ref "L11") (pin "1") (pinfunction "1_1") (pintype "passive"))
      (node (ref "L12") (pin "1") (pinfunction "1_1") (pintype "passive"))
      (node (ref "L2") (pin "1") (pinfunction "1_1") (pintype "passive"))
      (node (ref "L3") (pin "1") (pinfunction "1_1") (pintype "passive"))
      (node (ref "L4") (pin "1") (pinfunction "1_1") (pintype "passive"))
      (node (ref "L5") (pin "1") (pinfunction "1_1") (pintype "passive"))
      (node (ref "L6") (pin "1") (pinfunction "1_1") (pintype "passive"))
      (node (ref "L7") (pin "1") (pinfunction "1_1") (pintype "passive"))
      (node (ref "L8") (pin "1") (pinfunction "1_1") (pintype "passive"))
      (node (ref "L9") (pin "1") (pinfunction "1_1") (pintype "passive"))
      (node (ref "Q1") (pin "3") (pinfunction "S_3") (pintype "passive"))
      (node (ref "Q3") (pin "2") (pinfunction "D_2") (pintype "passive"))
      (node (ref "R4") (pin "1") (pinfunction "1_1") (pintype "passive"))
      (node (ref "U7") (pin "28") (pinfunction "HSA_28") (pintype "passive"))
    )
    (net (code "24") (name "/HS_B") (class "Default")
      (node (ref "C19") (pin "2") (pinfunction "2_2") (pintype "passive"))
      (node (ref "C54") (pin "2") (pinfunction "2_2") (pintype "passive"))
      (node (ref "D7") (pin "2") (pinfunction "A_2") (pintype "passive"))
      (node (ref "D9") (pin "1") (pinfunction "K_1") (pintype "passive"))
      (node (ref "L1") (pin "2") (pinfunction "2_2") (pintype "passive"))
      (node (ref "L10") (pin "2") (pinfunction "2_2") (pintype "passive"))
      (node (ref "L11") (pin "2") (pinfunction "2_2") (pintype "passive"))
      (node (ref "L12") (pin "2") (pinfunction "2_2") (pintype "passive"))
      (node (ref "L2") (pin "2") (pinfunction "2_2") (pintype "passive"))
      (node (ref "L3") (pin "2") (pinfunction "2_2") (pintype "passive"))
      (node (ref "L4") (pin "2") (pinfunction "2_2") (pintype "passive"))
      (node (ref "L5") (pin "2") (pinfunction "2_2") (pintype "passive"))
      (node (ref "L6") (pin "2") (pinfunction "2_2") (pintype "passive"))
      (node (ref "L7") (pin "2") (pinfunction "2_2") (pintype "passive"))
      (node (ref "L8") (pin "2") (pinfunction "2_2") (pintype "passive"))
      (node (ref "L9") (pin "2") (pinfunction "2_2") (pintype "passive"))
      (node (ref "Q2") (pin "3") (pinfunction "S_3") (pintype "passive"))
      (node (ref "Q4") (pin "2") (pinfunction "D_2") (pintype "passive"))
      (node (ref "R3") (pin "2") (pinfunction "2_2") (pintype "passive"))
      (node (ref "U7") (pin "18") (pinfunction "HSB_18") (pintype "passive"))
    )
    (net (code "25") (name "/IIN") (class "Default")
      (node (ref "C61") (pin "2") (pinfunction "2_2") (pintype "passive"))
      (node (ref "R56") (pin "2") (pinfunction "2_2") (pintype "passive"))
      (node (ref "U7") (pin "3") (pinfunction "IIN_3") (pintype "output"))
    )
    (net (code "26") (name "/IOUT") (class "Default")
      (node (ref "C62") (pin "2") (pinfunction "2_2") (pintype "passive"))
      (node (ref "R116") (pin "2") (pinfunction "2_2") (pintype "passive"))
      (node (ref "U7") (pin "12") (pinfunction "IOUT_12") (pintype "output"))
    )
    (net (code "27") (name "/LED_A") (class "Default")
      (node (ref "J1") (pin "9") (pinfunction "9_9") (pintype "passive"))
      (node (ref "J2") (pin "11") (pinfunction "11_11") (pintype "passive"))
      (node (ref "R_LEDB_O") (pin "2") (pinfunction "2_2") (pintype "passive"))
    )
    (net (code "28") (name "/LED_B") (class "Default")
      (node (ref "J1") (pin "11") (pinfunction "11_11") (pintype "passive"))
      (node (ref "J2") (pin "9") (pinfunction "9_9") (pintype "passive"))
      (node (ref "R_LEDA_O") (pin "2") (pinfunction "2_2") (pintype "passive"))
    )
    (net (code "29") (name "/LED_VSS") (class "Default")
      (node (ref "Q_LEDA") (pin "2") (pinfunction "S_2") (pintype "passive"))
      (node (ref "Q_LEDB") (pin "2") (pinfunction "S_2") (pintype "passive"))
      (node (ref "Q_LEDVSS") (pin "3") (pinfunction "D_3") (pintype "passive"))
    )
    (net (code "30") (name "/LIA") (class "Default")
      (node (ref "U7") (pin "6") (pinfunction "LIA_6") (pintype "input"))
      (node (ref "U8") (pin "27") (pinfunction "LIA_27") (pintype "output"))
    )
    (net (code "31") (name "/LIB") (class "Default")
      (node (ref "U7") (pin "9") (pinfunction "LIB_9") (pintype "input"))
      (node (ref "U8") (pin "24") (pinfunction "LIB_24") (pintype "output"))
    )
    (net (code "32") (name "/LO_A") (class "Default")
      (node (ref "D5") (pin "1") (pinfunction "K_1") (pintype "passive"))
      (node (ref "R32") (pin "1") (pinfunction "1_1") (pintype "passive"))
      (node (ref "R32_a") (pin "1") (pinfunction "1_1") (pintype "passive"))
      (node (ref "U7") (pin "24") (pinfunction "LOA_24") (pintype "output"))
    )
    (net (code "33") (name "/LO_B") (class "Default")
      (node (ref "D6") (pin "1") (pinfunction "K_1") (pintype "passive"))
      (node (ref "R33") (pin "2") (pinfunction "2_2") (pintype "passive"))
      (node (ref "R33_a") (pin "2") (pinfunction "2_2") (pintype "passive"))
      (node (ref "U7") (pin "22") (pinfunction "LOB_22") (pintype "output"))
    )
    (net (code "34") (name "/NC4") (class "Default")
      (node (ref "C69") (pin "2") (pinfunction "2_2") (pintype "passive"))
      (node (ref "R87_a") (pin "1") (pinfunction "1_1") (pintype "passive"))
      (node (ref "U8") (pin "23") (pinfunction "NC4_23") (pintype "passive"))
    )
    (net (code "35") (name "/OVS") (class "Default")
      (node (ref "R121") (pin "1") (pinfunction "1_1") (pintype "passive"))
      (node (ref "U7") (pin "16") (pinfunction "OVS_16") (pintype "passive"))
    )
    (net (code "36") (name "/PAN_DET") (class "Default")
      (node (ref "D_1A") (pin "1") (pinfunction "K_1") (pintype "passive"))
      (node (ref "D_1B") (pin "1") (pinfunction "K_1") (pintype "passive"))
      (node (ref "Q_LEDVSS") (pin "1") (pinfunction "G_1") (pintype "passive"))
    )
    (net (code "37") (name "/PM") (class "Default")
      (node (ref "U8") (pin "28") (pinfunction "PM_28") (pintype "input"))
    )
    (net (code "38") (name "/RST") (class "Default")
      (node (ref "U7") (pin "10") (pinfunction "PGD_10") (pintype "open_collector"))
    )
    (net (code "39") (name "/SOL_1A") (class "Default")
      (node (ref "D1_a") (pin "2") (pinfunction "A_2") (pintype "passive"))
      (node (ref "D1_b") (pin "2") (pinfunction "A_2") (pintype "passive"))
      (node (ref "D1_c") (pin "2") (pinfunction "A_2") (pintype "passive"))
      (node (ref "D1_d") (pin "2") (pinfunction "A_2") (pintype "passive"))
      (node (ref "D1_e") (pin "2") (pinfunction "A_2") (pintype "passive"))
      (node (ref "D1_f") (pin "2") (pinfunction "A_2") (pintype "passive"))
      (node (ref "D3_a") (pin "1") (pinfunction "K_1") (pintype "passive"))
      (node (ref "D3_b") (pin "1") (pinfunction "K_1") (pintype "passive"))
      (node (ref "D3_c") (pin "1") (pinfunction "K_1") (pintype "passive"))
      (node (ref "D3_d") (pin "1") (pinfunction "K_1") (pintype "passive"))
      (node (ref "D3_e") (pin "1") (pinfunction "K_1") (pintype "passive"))
      (node (ref "D3_f") (pin "1") (pinfunction "K_1") (pintype "passive"))
      (node (ref "J1") (pin "1") (pinfunction "1_1") (pintype "passive"))
      (node (ref "J1") (pin "2") (pinfunction "2_2") (pintype "passive"))
      (node (ref "J1") (pin "3") (pinfunction "3_3") (pintype "passive"))
      (node (ref "J1") (pin "4") (pinfunction "4_4") (pintype "passive"))
      (node (ref "J1") (pin "5") (pinfunction "5_5") (pintype "passive"))
      (node (ref "J1") (pin "6") (pinfunction "6_6") (pintype "passive"))
      (node (ref "J1") (pin "7") (pinfunction "7_7") (pintype "passive"))
      (node (ref "J1") (pin "8") (pinfunction "8_8") (pintype "passive"))
      (node (ref "J_IN") (pin "PLUS") (pinfunction "+_PLUS") (pintype "passive"))
      (node (ref "R_1A_a") (pin "1") (pinfunction "1_1") (pintype "passive"))
    )
    (net (code "40") (name "/SOL_1B") (class "Default")
      (node (ref "D2_a") (pin "2") (pinfunction "A_2") (pintype "passive"))
      (node (ref "D2_b") (pin "2") (pinfunction "A_2") (pintype "passive"))
      (node (ref "D2_c") (pin "2") (pinfunction "A_2") (pintype "passive"))
      (node (ref "D2_d") (pin "2") (pinfunction "A_2") (pintype "passive"))
      (node (ref "D2_e") (pin "2") (pinfunction "A_2") (pintype "passive"))
      (node (ref "D2_f") (pin "2") (pinfunction "A_2") (pintype "passive"))
      (node (ref "D4_a") (pin "1") (pinfunction "K_1") (pintype "passive"))
      (node (ref "D4_b") (pin "1") (pinfunction "K_1") (pintype "passive"))
      (node (ref "D4_c") (pin "1") (pinfunction "K_1") (pintype "passive"))
      (node (ref "D4_d") (pin "1") (pinfunction "K_1") (pintype "passive"))
      (node (ref "D4_e") (pin "1") (pinfunction "K_1") (pintype "passive"))
      (node (ref "D4_f") (pin "1") (pinfunction "K_1") (pintype "passive"))
      (node (ref "J2") (pin "1") (pinfunction "1_1") (pintype "passive"))
      (node (ref "J2") (pin "2") (pinfunction "2_2") (pintype "passive"))
      (node (ref "J2") (pin "3") (pinfunction "3_3") (pintype "passive"))
      (node (ref "J2") (pin "4") (pinfunction "4_4") (pintype "passive"))
      (node (ref "J2") (pin "5") (pinfunction "5_5") (pintype "passive"))
      (node (ref "J2") (pin "6") (pinfunction "6_6") (pintype "passive"))
      (node (ref "J2") (pin "7") (pinfunction "7_7") (pintype "passive"))
      (node (ref "J2") (pin "8") (pinfunction "8_8") (pintype "passive"))
      (node (ref "J_IN") (pin "MINUS") (pinfunction "-_MINUS") (pintype "passive"))
      (node (ref "R_1B_a") (pin "1") (pinfunction "1_1") (pintype "passive"))
    )
    (net (code "41") (name "/VOUT_N") (class "Default")
      (node (ref "J_OUT") (pin "PLUS") (pinfunction "+_PLUS") (pintype "passive"))
      (node (ref "R10") (pin "2") (pinfunction "2_2") (pintype "passive"))
      (node (ref "RA1_N") (pin "1") (pinfunction "1_1") (pintype "passive"))
    )
    (net (code "42") (name "/nRST") (class "Default")
      (node (ref "C66") (pin "2") (pinfunction "2_2") (pintype "passive"))
      (node (ref "R26") (pin "1") (pinfunction "1_1") (pintype "passive"))
      (node (ref "U8") (pin "1") (pinfunction "RST_1") (pintype "input"))
    )
    (net (code "43") (name "10VDC") (class "Default")
      (node (ref "C23_a") (pin "1") (pinfunction "1_1") (pintype "passive"))
      (node (ref "C23_b") (pin "1") (pinfunction "1_1") (pintype "passive"))
      (node (ref "C23_c") (pin "1") (pinfunction "1_1") (pintype "passive"))
      (node (ref "C23_d") (pin "1") (pinfunction "1_1") (pintype "passive"))
      (node (ref "C23_e") (pin "1") (pinfunction "1_1") (pintype "passive"))
      (node (ref "C23_f") (pin "1") (pinfunction "1_1") (pintype "passive"))
      (node (ref "C23_g") (pin "1") (pinfunction "1_1") (pintype "passive"))
      (node (ref "C24") (pin "2") (pinfunction "2_2") (pintype "passive"))
      (node (ref "C31") (pin "1") (pinfunction "1_1") (pintype "passive"))
      (node (ref "C35") (pin "1") (pinfunction "1_1") (pintype "passive"))
      (node (ref "C40") (pin "2") (pinfunction "2_2") (pintype "passive"))
      (node (ref "L0") (pin "2") (pinfunction "2_2") (pintype "passive"))
      (node (ref "R9") (pin "1") (pinfunction "1_1") (pintype "passive"))
      (node (ref "U5V") (pin "1") (pinfunction "VIN_1") (pintype "input"))
      (node (ref "U7") (pin "21") (pinfunction "VCC1_21") (pintype "power_in"))
      (node (ref "U7") (pin "25") (pinfunction "VCC2_25") (pintype "power_in"))
    )
    (net (code "44") (name "AGND") (class "Default")
      (node (ref "C61") (pin "1") (pinfunction "1_1") (pintype "passive"))
      (node (ref "C62") (pin "1") (pinfunction "1_1") (pintype "passive"))
      (node (ref "NT2") (pin "1") (pinfunction "1_1") (pintype "passive"))
      (node (ref "R116") (pin "1") (pinfunction "1_1") (pintype "passive"))
      (node (ref "R56") (pin "1") (pinfunction "1_1") (pintype "passive"))
      (node (ref "U7") (pin "5") (pinfunction "AGND_5") (pintype "power_in"))
      (node (ref "U8") (pin "13") (pinfunction "VSSA_13") (pintype "power_in"))
    )
    (net (code "45") (name "GND") (class "Default")
      (node (ref "C15") (pin "2") (pinfunction "2_2") (pintype "passive"))
      (node (ref "C21") (pin "1") (pinfunction "1_1") (pintype "passive"))
      (node (ref "C22") (pin "1") (pinfunction "1_1") (pintype "passive"))
      (node (ref "C23_a") (pin "2") (pinfunction "2_2") (pintype "passive"))
      (node (ref "C23_b") (pin "2") (pinfunction "2_2") (pintype "passive"))
      (node (ref "C23_c") (pin "2") (pinfunction "2_2") (pintype "passive"))
      (node (ref "C23_d") (pin "2") (pinfunction "2_2") (pintype "passive"))
      (node (ref "C23_e") (pin "2") (pinfunction "2_2") (pintype "passive"))
      (node (ref "C23_f") (pin "2") (pinfunction "2_2") (pintype "passive"))
      (node (ref "C23_g") (pin "2") (pinfunction "2_2") (pintype "passive"))
      (node (ref "C26") (pin "1") (pinfunction "1_1") (pintype "passive"))
      (node (ref "C29") (pin "1") (pinfunction "1_1") (pintype "passive"))
      (node (ref "C31") (pin "2") (pinfunction "2_2") (pintype "passive"))
      (node (ref "C32") (pin "1") (pinfunction "1_1") (pintype "passive"))
      (node (ref "C33") (pin "2") (pinfunction "2_2") (pintype "passive"))
      (node (ref "C34") (pin "1") (pinfunction "1_1") (pintype "passive"))
      (node (ref "C35") (pin "2") (pinfunction "2_2") (pintype "passive"))
      (node (ref "C37") (pin "2") (pinfunction "2_2") (pintype "passive"))
      (node (ref "C38") (pin "1") (pinfunction "1_1") (pintype "passive"))
      (node (ref "C39") (pin "1") (pinfunction "1_1") (pintype "passive"))
      (node (ref "C40") (pin "1") (pinfunction "1_1") (pintype "passive"))
      (node (ref "C42") (pin "1") (pinfunction "1_1") (pintype "passive"))
      (node (ref "C49") (pin "1") (pinfunction "1_1") (pintype "passive"))
      (node (ref "C50") (pin "1") (pinfunction "1_1") (pintype "passive"))
      (node (ref "C51") (pin "1") (pinfunction "1_1") (pintype "passive"))
      (node (ref "C52") (pin "2") (pinfunction "2_2") (pintype "passive"))
      (node (ref "C58") (pin "1") (pinfunction "1_1") (pintype "passive"))
      (node (ref "C59") (pin "1") (pinfunction "1_1") (pintype "passive"))
      (node (ref "C60") (pin "1") (pinfunction "1_1") (pintype "passive"))
      (node (ref "C64") (pin "1") (pinfunction "1_1") (pintype "passive"))
      (node (ref "C66") (pin "1") (pinfunction "1_1") (pintype "passive"))
      (node (ref "C69") (pin "1") (pinfunction "1_1") (pintype "passive"))
      (node (ref "D2") (pin "2") (pinfunction "A_2") (pintype "passive"))
      (node (ref "D_1A_G") (pin "2") (pinfunction "A_2") (pintype "passive"))
      (node (ref "D_1B_G") (pin "2") (pinfunction "A_2") (pintype "passive"))
      (node (ref "NT2") (pin "2") (pinfunction "2_2") (pintype "passive"))
      (node (ref "Q_LEDVSS") (pin "2") (pinfunction "S_2") (pintype "passive"))
      (node (ref "R121") (pin "2") (pinfunction "2_2") (pintype "passive"))
      (node (ref "R15") (pin "1") (pinfunction "1_1") (pintype "passive"))
      (node (ref "R20") (pin "2") (pinfunction "2_2") (pintype "passive"))
      (node (ref "R25") (pin "1") (pinfunction "1_1") (pintype "passive"))
      (node (ref "R35") (pin "1") (pinfunction "1_1") (pintype "passive"))
      (node (ref "R38") (pin "1") (pinfunction "1_1") (pintype "passive"))
      (node (ref "R39") (pin "1") (pinfunction "1_1") (pintype "passive"))
      (node (ref "R40") (pin "1") (pinfunction "1_1") (pintype "passive"))
      (node (ref "R41") (pin "1") (pinfunction "1_1") (pintype "passive"))
      (node (ref "R42") (pin "1") (pinfunction "1_1") (pintype "passive"))
      (node (ref "R43") (pin "1") (pinfunction "1_1") (pintype "passive"))
      (node (ref "R53") (pin "2") (pinfunction "2_2") (pintype "passive"))
      (node (ref "R5_a") (pin "1") (pinfunction "1_1") (pintype "passive"))
      (node (ref "R_1A_c") (pin "1") (pinfunction "1_1") (pintype "passive"))
      (node (ref "R_1B_c") (pin "1") (pinfunction "1_1") (pintype "passive"))
      (node (ref "U1") (pin "4") (pinfunction "RTN_4") (pintype "bidirectional"))
      (node (ref "U5V") (pin "2") (pinfunction "GND_2") (pintype "power_in"))
      (node (ref "U7") (pin "23") (pinfunction "PGND_23") (pintype "power_in"))
      (node (ref "U8") (pin "4") (pinfunction "VSSD_4") (pintype "power_in"))
    )
    (net (code "46") (name "GND_IN") (class "Default")
      (node (ref "D3_a") (pin "2") (pinfunction "A_2") (pintype "passive"))
      (node (ref "D3_b") (pin "2") (pinfunction "A_2") (pintype "passive"))
      (node (ref "D3_c") (pin "2") (pinfunction "A_2") (pintype "passive"))
      (node (ref "D3_d") (pin "2") (pinfunction "A_2") (pintype "passive"))
      (node (ref "D3_e") (pin "2") (pinfunction "A_2") (pintype "passive"))
      (node (ref "D3_f") (pin "2") (pinfunction "A_2") (pintype "passive"))
      (node (ref "D4_a") (pin "2") (pinfunction "A_2") (pintype "passive"))
      (node (ref "D4_b") (pin "2") (pinfunction "A_2") (pintype "passive"))
      (node (ref "D4_c") (pin "2") (pinfunction "A_2") (pintype "passive"))
      (node (ref "D4_d") (pin "2") (pinfunction "A_2") (pintype "passive"))
      (node (ref "D4_e") (pin "2") (pinfunction "A_2") (pintype "passive"))
      (node (ref "D4_f") (pin "2") (pinfunction "A_2") (pintype "passive"))
      (node (ref "D_CLAMP_18") (pin "2") (pinfunction "A_2") (pintype "passive"))
    )
    (net (code "47") (name "Net-(D2-K)") (class "Default")
      (node (ref "C17") (pin "2") (pinfunction "2_2") (pintype "passive"))
      (node (ref "D2") (pin "1") (pinfunction "K_1") (pintype "passive"))
      (node (ref "L0") (pin "1") (pinfunction "1_1") (pintype "passive"))
      (node (ref "U1") (pin "1") (pinfunction "SW_1") (pintype "bidirectional"))
    )
    (net (code "48") (name "Net-(D3-A)") (class "Default")
      (node (ref "D3") (pin "2") (pinfunction "A_2") (pintype "passive"))
      (node (ref "Q1") (pin "1") (pinfunction "G_1") (pintype "passive"))
      (node (ref "R18") (pin "2") (pinfunction "2_2") (pintype "passive"))
      (node (ref "R18_a") (pin "2") (pinfunction "2_2") (pintype "passive"))
      (node (ref "R4") (pin "2") (pinfunction "2_2") (pintype "passive"))
    )
    (net (code "49") (name "Net-(D4-A)") (class "Default")
      (node (ref "D4") (pin "2") (pinfunction "A_2") (pintype "passive"))
      (node (ref "Q2") (pin "1") (pinfunction "G_1") (pintype "passive"))
      (node (ref "R19") (pin "1") (pinfunction "1_1") (pintype "passive"))
      (node (ref "R19_a") (pin "1") (pinfunction "1_1") (pintype "passive"))
      (node (ref "R3") (pin "1") (pinfunction "1_1") (pintype "passive"))
    )
    (net (code "50") (name "Net-(D5-A)") (class "Default")
      (node (ref "D5") (pin "2") (pinfunction "A_2") (pintype "passive"))
      (node (ref "Q3") (pin "1") (pinfunction "G_1") (pintype "passive"))
      (node (ref "R22") (pin "2") (pinfunction "2_2") (pintype "passive"))
      (node (ref "R32") (pin "2") (pinfunction "2_2") (pintype "passive"))
      (node (ref "R32_a") (pin "2") (pinfunction "2_2") (pintype "passive"))
    )
    (net (code "51") (name "Net-(D6-A)") (class "Default")
      (node (ref "D6") (pin "2") (pinfunction "A_2") (pintype "passive"))
      (node (ref "Q4") (pin "1") (pinfunction "G_1") (pintype "passive"))
      (node (ref "R23") (pin "1") (pinfunction "1_1") (pintype "passive"))
      (node (ref "R33") (pin "1") (pinfunction "1_1") (pintype "passive"))
      (node (ref "R33_a") (pin "1") (pinfunction "1_1") (pintype "passive"))
    )
    (net (code "52") (name "Net-(D14-A)") (class "Default")
      (node (ref "C19") (pin "1") (pinfunction "1_1") (pintype "passive"))
      (node (ref "D14") (pin "2") (pinfunction "A_2") (pintype "passive"))
      (node (ref "R14") (pin "2") (pinfunction "2_2") (pintype "passive"))
    )
    (net (code "53") (name "Net-(D15-A)") (class "Default")
      (node (ref "C18") (pin "1") (pinfunction "1_1") (pintype "passive"))
      (node (ref "D15") (pin "2") (pinfunction "A_2") (pintype "passive"))
      (node (ref "R11") (pin "2") (pinfunction "2_2") (pintype "passive"))
    )
    (net (code "54") (name "Net-(D_CLAMP_1-A)") (class "Default")
      (node (ref "D_CLAMP_1") (pin "2") (pinfunction "A_2") (pintype "passive"))
      (node (ref "D_CLAMP_2") (pin "1") (pinfunction "K_1") (pintype "passive"))
    )
    (net (code "55") (name "Net-(D_CLAMP_2-A)") (class "Default")
      (node (ref "D_CLAMP_2") (pin "2") (pinfunction "A_2") (pintype "passive"))
      (node (ref "D_CLAMP_3") (pin "1") (pinfunction "K_1") (pintype "passive"))
    )
    (net (code "56") (name "Net-(D_CLAMP_3-A)") (class "Default")
      (node (ref "D_CLAMP_3") (pin "2") (pinfunction "A_2") (pintype "passive"))
      (node (ref "D_CLAMP_4") (pin "1") (pinfunction "K_1") (pintype "passive"))
    )
    (net (code "57") (name "Net-(D_CLAMP_4-A)") (class "Default")
      (node (ref "D_CLAMP_4") (pin "2") (pinfunction "A_2") (pintype "passive"))
      (node (ref "D_CLAMP_5") (pin "1") (pinfunction "K_1") (pintype "passive"))
    )
    (net (code "58") (name "Net-(D_CLAMP_5-A)") (class "Default")
      (node (ref "D_CLAMP_5") (pin "2") (pinfunction "A_2") (pintype "passive"))
      (node (ref "D_CLAMP_6") (pin "1") (pinfunction "K_1") (pintype "passive"))
    )
    (net (code "59") (name "Net-(D_CLAMP_6-A)") (class "Default")
      (node (ref "D_CLAMP_6") (pin "2") (pinfunction "A_2") (pintype "passive"))
      (node (ref "D_CLAMP_7") (pin "1") (pinfunction "K_1") (pintype "passive"))
    )
    (net (code "60") (name "Net-(D_CLAMP_7-A)") (class "Default")
      (node (ref "D_CLAMP_7") (pin "2") (pinfunction "A_2") (pintype "passive"))
      (node (ref "D_CLAMP_8") (pin "1") (pinfunction "K_1") (pintype "passive"))
      (node (ref "R16") (pin "2") (pinfunction "2_2") (pintype "passive"))
    )
    (net (code "61") (name "Net-(D_CLAMP_8-A)") (class "Default")
      (node (ref "D_CLAMP_8") (pin "2") (pinfunction "A_2") (pintype "passive"))
      (node (ref "D_CLAMP_9") (pin "1") (pinfunction "K_1") (pintype "passive"))
    )
    (net (code "62") (name "Net-(D_CLAMP_10-A)") (class "Default")
      (node (ref "D_CLAMP_10") (pin "2") (pinfunction "A_2") (pintype "passive"))
      (node (ref "D_CLAMP_11") (pin "1") (pinfunction "K_1") (pintype "passive"))
    )
    (net (code "63") (name "Net-(D_CLAMP_10-K)") (class "Default")
      (node (ref "D_CLAMP_10") (pin "1") (pinfunction "K_1") (pintype "passive"))
      (node (ref "D_CLAMP_9") (pin "2") (pinfunction "A_2") (pintype "passive"))
      (node (ref "R16") (pin "1") (pinfunction "1_1") (pintype "passive"))
    )
    (net (code "64") (name "Net-(D_CLAMP_11-A)") (class "Default")
      (node (ref "D_CLAMP_11") (pin "2") (pinfunction "A_2") (pintype "passive"))
      (node (ref "D_CLAMP_12") (pin "1") (pinfunction "K_1") (pintype "passive"))
    )
    (net (code "65") (name "Net-(D_CLAMP_12-A)") (class "Default")
      (node (ref "D_CLAMP_12") (pin "2") (pinfunction "A_2") (pintype "passive"))
      (node (ref "D_CLAMP_13") (pin "1") (pinfunction "K_1") (pintype "passive"))
    )
    (net (code "66") (name "Net-(D_CLAMP_13-A)") (class "Default")
      (node (ref "D_CLAMP_13") (pin "2") (pinfunction "A_2") (pintype "passive"))
      (node (ref "D_CLAMP_14") (pin "1") (pinfunction "K_1") (pintype "passive"))
    )
    (net (code "67") (name "Net-(D_CLAMP_14-A)") (class "Default")
      (node (ref "D_CLAMP_14") (pin "2") (pinfunction "A_2") (pintype "passive"))
      (node (ref "D_CLAMP_15") (pin "1") (pinfunction "K_1") (pintype "passive"))
    )
    (net (code "68") (name "Net-(D_CLAMP_15-A)") (class "Default")
      (node (ref "D_CLAMP_15") (pin "2") (pinfunction "A_2") (pintype "passive"))
      (node (ref "D_CLAMP_16") (pin "1") (pinfunction "K_1") (pintype "passive"))
    )
    (net (code "69") (name "Net-(D_CLAMP_16-A)") (class "Default")
      (node (ref "D_CLAMP_16") (pin "2") (pinfunction "A_2") (pintype "passive"))
      (node (ref "D_CLAMP_17") (pin "1") (pinfunction "K_1") (pintype "passive"))
    )
    (net (code "70") (name "Net-(D_CLAMP_17-A)") (class "Default")
      (node (ref "D_CLAMP_17") (pin "2") (pinfunction "A_2") (pintype "passive"))
      (node (ref "D_CLAMP_18") (pin "1") (pinfunction "K_1") (pintype "passive"))
    )
    (net (code "71") (name "Net-(J1-Pad10)") (class "Default")
      (node (ref "J1") (pin "10") (pinfunction "10_10") (pintype "passive"))
      (node (ref "R101") (pin "2") (pinfunction "2_2") (pintype "passive"))
    )
    (net (code "72") (name "Net-(J1-Pad12)") (class "Default")
      (node (ref "J1") (pin "12") (pinfunction "12_12") (pintype "passive"))
      (node (ref "R100") (pin "2") (pinfunction "2_2") (pintype "passive"))
    )
    (net (code "73") (name "Net-(J1-SHIELD-PadS1)") (class "Default")
      (node (ref "J1") (pin "S1") (pinfunction "SHIELD_S1") (pintype "passive"))
      (node (ref "J1") (pin "S2") (pinfunction "SHIELD_S2") (pintype "passive"))
    )
    (net (code "74") (name "Net-(J2-Pad10)") (class "Default")
      (node (ref "J2") (pin "10") (pinfunction "10_10") (pintype "passive"))
      (node (ref "R102") (pin "2") (pinfunction "2_2") (pintype "passive"))
    )
    (net (code "75") (name "Net-(J2-Pad12)") (class "Default")
      (node (ref "J2") (pin "12") (pinfunction "12_12") (pintype "passive"))
      (node (ref "R103") (pin "2") (pinfunction "2_2") (pintype "passive"))
    )
    (net (code "76") (name "Net-(J2-SHIELD-PadS1)") (class "Default")
      (node (ref "J2") (pin "S1") (pinfunction "SHIELD_S1") (pintype "passive"))
      (node (ref "J2") (pin "S2") (pinfunction "SHIELD_S2") (pintype "passive"))
    )
    (net (code "77") (name "Net-(Q_LEDA-D)") (class "Default")
      (node (ref "Q_LEDA") (pin "3") (pinfunction "D_3") (pintype "passive"))
      (node (ref "Q_LEDB") (pin "1") (pinfunction "G_1") (pintype "passive"))
      (node (ref "R_LEDB_O") (pin "1") (pinfunction "1_1") (pintype "passive"))
    )
    (net (code "78") (name "Net-(Q_LEDB-D)") (class "Default")
      (node (ref "Q_LEDB") (pin "3") (pinfunction "D_3") (pintype "passive"))
      (node (ref "R_LEDA_O") (pin "1") (pinfunction "1_1") (pintype "passive"))
    )
    (net (code "79") (name "Net-(R5-Pad1)") (class "Default")
      (node (ref "R5") (pin "1") (pinfunction "1_1") (pintype "passive"))
      (node (ref "R5_a") (pin "2") (pinfunction "2_2") (pintype "passive"))
    )
    (net (code "80") (name "Net-(R8-Pad2)") (class "Default")
      (node (ref "R8") (pin "2") (pinfunction "2_2") (pintype "passive"))
      (node (ref "R8_A") (pin "1") (pinfunction "1_1") (pintype "passive"))
    )
    (net (code "81") (name "Net-(R12-Pad2)") (class "Default")
      (node (ref "R12") (pin "2") (pinfunction "2_2") (pintype "passive"))
      (node (ref "R12_A") (pin "1") (pinfunction "1_1") (pintype "passive"))
    )
    (net (code "82") (name "Net-(R24-Pad2)") (class "Default")
      (node (ref "R24") (pin "2") (pinfunction "2_2") (pintype "passive"))
      (node (ref "R24_A") (pin "1") (pinfunction "1_1") (pintype "passive"))
    )
    (net (code "83") (name "Net-(R24_B-Pad1)") (class "Default")
      (node (ref "R24_B") (pin "1") (pinfunction "1_1") (pintype "passive"))
      (node (ref "R34") (pin "2") (pinfunction "2_2") (pintype "passive"))
    )
    (net (code "84") (name "Net-(R_1A_a-Pad2)") (class "Default")
      (node (ref "R_1A_a") (pin "2") (pinfunction "2_2") (pintype "passive"))
      (node (ref "R_1A_b") (pin "1") (pinfunction "1_1") (pintype "passive"))
    )
    (net (code "85") (name "Net-(R_1B_a-Pad2)") (class "Default")
      (node (ref "R_1B_a") (pin "2") (pinfunction "2_2") (pintype "passive"))
      (node (ref "R_1B_b") (pin "1") (pinfunction "1_1") (pintype "passive"))
    )
    (net (code "86") (name "Net-(Ron_a-Pad1)") (class "Default")
      (node (ref "Ron_a") (pin "1") (pinfunction "1_1") (pintype "passive"))
      (node (ref "Ron_b") (pin "1") (pinfunction "1_1") (pintype "passive"))
    )
    (net (code "87") (name "Net-(Ron_b-Pad2)") (class "Default")
      (node (ref "Ron_b") (pin "2") (pinfunction "2_2") (pintype "passive"))
      (node (ref "Ron_c") (pin "2") (pinfunction "2_2") (pintype "passive"))
      (node (ref "Ron_d") (pin "2") (pinfunction "2_2") (pintype "passive"))
    )
    (net (code "88") (name "Net-(U1-BST)") (class "Default")
      (node (ref "C17") (pin "1") (pinfunction "1_1") (pintype "passive"))
      (node (ref "U1") (pin "2") (pinfunction "BST_2") (pintype "bidirectional"))
    )
    (net (code "89") (name "Net-(U1-FB)") (class "Default")
      (node (ref "C24") (pin "1") (pinfunction "1_1") (pintype "passive"))
      (node (ref "R15") (pin "2") (pinfunction "2_2") (pintype "passive"))
      (node (ref "R9") (pin "2") (pinfunction "2_2") (pintype "passive"))
      (node (ref "U1") (pin "5") (pinfunction "FB_5") (pintype "bidirectional"))
    )
    (net (code "90") (name "Net-(U1-RCL)") (class "Default")
      (node (ref "R5") (pin "2") (pinfunction "2_2") (pintype "passive"))
      (node (ref "U1") (pin "3") (pinfunction "RCL_3") (pintype "input"))
    )
    (net (code "91") (name "Net-(U1-RT{slash}SD)") (class "Default")
      (node (ref "Ron_a") (pin "2") (pinfunction "2_2") (pintype "passive"))
      (node (ref "U1") (pin "6") (pinfunction "RT/SD_6") (pintype "input"))
    )
    (net (code "92") (name "Net-(U1-VCC)") (class "Default")
      (node (ref "C15") (pin "1") (pinfunction "1_1") (pintype "passive"))
      (node (ref "U1") (pin "7") (pinfunction "VCC_7") (pintype "power_in"))
    )
    (net (code "93") (name "Net-(U5V-Vout)") (class "Default")
      (node (ref "R17") (pin "1") (pinfunction "1_1") (pintype "passive"))
      (node (ref "U5V") (pin "3") (pinfunction "Vout_3") (pintype "output"))
    )
    (net (code "94") (name "Net-(U7-HBA)") (class "Default")
      (node (ref "C46") (pin "1") (pinfunction "1_1") (pintype "passive"))
      (node (ref "U7") (pin "26") (pinfunction "HBA_26") (pintype "passive"))
    )
    (net (code "95") (name "Net-(U7-HBB)") (class "Default")
      (node (ref "C54") (pin "1") (pinfunction "1_1") (pintype "passive"))
      (node (ref "U7") (pin "20") (pinfunction "HBB_20") (pintype "passive"))
    )
    (net (code "96") (name "Net-(U7-SDA)") (class "Default")
      (node (ref "R8_A") (pin "2") (pinfunction "2_2") (pintype "passive"))
      (node (ref "U7") (pin "2") (pinfunction "SDA_2") (pintype "input"))
    )
    (net (code "97") (name "Net-(U7-SIA)") (class "Default")
      (node (ref "R12_A") (pin "2") (pinfunction "2_2") (pintype "passive"))
      (node (ref "U7") (pin "1") (pinfunction "SIA_1") (pintype "input"))
    )
    (net (code "98") (name "Net-(U7-SIB)") (class "Default")
      (node (ref "R24") (pin "1") (pinfunction "1_1") (pintype "passive"))
      (node (ref "U7") (pin "14") (pinfunction "SIB_14") (pintype "input"))
    )
    (net (code "99") (name "Net-(U7-SOB)") (class "Default")
      (node (ref "R34") (pin "1") (pinfunction "1_1") (pintype "passive"))
      (node (ref "U7") (pin "13") (pinfunction "SOB_13") (pintype "output"))
    )
    (net (code "100") (name "Net-(U8-A0)") (class "Default")
      (node (ref "C49") (pin "2") (pinfunction "2_2") (pintype "passive"))
      (node (ref "R28") (pin "1") (pinfunction "1_1") (pintype "passive"))
      (node (ref "R38") (pin "2") (pinfunction "2_2") (pintype "passive"))
      (node (ref "U8") (pin "14") (pinfunction "A0_14") (pintype "bidirectional"))
    )
    (net (code "101") (name "Net-(U8-A2)") (class "Default")
      (node (ref "C50") (pin "2") (pinfunction "2_2") (pintype "passive"))
      (node (ref "R29") (pin "1") (pinfunction "1_1") (pintype "passive"))
      (node (ref "R39") (pin "2") (pinfunction "2_2") (pintype "passive"))
      (node (ref "U8") (pin "16") (pinfunction "A2_16") (pintype "bidirectional"))
    )
    (net (code "102") (name "Net-(U8-A4)") (class "Default")
      (node (ref "C51") (pin "2") (pinfunction "2_2") (pintype "passive"))
      (node (ref "R30") (pin "2") (pinfunction "2_2") (pintype "passive"))
      (node (ref "R40") (pin "2") (pinfunction "2_2") (pintype "passive"))
      (node (ref "U8") (pin "18") (pinfunction "A4_18") (pintype "bidirectional"))
    )
    (net (code "103") (name "Net-(U8-A6)") (class "Default")
      (node (ref "C52") (pin "1") (pinfunction "1_1") (pintype "passive"))
      (node (ref "R31") (pin "1") (pinfunction "1_1") (pintype "passive"))
      (node (ref "R41") (pin "2") (pinfunction "2_2") (pintype "passive"))
      (node (ref "U8") (pin "20") (pinfunction "A6_20") (pintype "bidirectional"))
    )
    (net (code "104") (name "Net-(U8-I2C0)") (class "Default")
      (node (ref "R36") (pin "2") (pinfunction "2_2") (pintype "passive"))
      (node (ref "U8") (pin "6") (pinfunction "I2C0_6") (pintype "bidirectional"))
    )
    (net (code "105") (name "Net-(U8-I2C1)") (class "Default")
      (node (ref "R42") (pin "2") (pinfunction "2_2") (pintype "passive"))
      (node (ref "U8") (pin "7") (pinfunction "I2C1_7") (pintype "bidirectional"))
    )
    (net (code "106") (name "Net-(U8-I2C2)") (class "Default")
      (node (ref "R43") (pin "2") (pinfunction "2_2") (pintype "passive"))
      (node (ref "U8") (pin "22") (pinfunction "I2C2_22") (pintype "bidirectional"))
    )
    (net (code "107") (name "Net-(U8-NC1)") (class "Default")
      (node (ref "R35") (pin "2") (pinfunction "2_2") (pintype "passive"))
      (node (ref "U8") (pin "2") (pinfunction "NC1_2") (pintype "passive"))
    )
    (net (code "108") (name "Net-(U8-NC2)") (class "Default")
      (node (ref "R45") (pin "2") (pinfunction "2_2") (pintype "passive"))
      (node (ref "U8") (pin "5") (pinfunction "NC2_5") (pintype "passive"))
    )
    (net (code "109") (name "Net-(U8-NC3)") (class "Default")
      (node (ref "R25") (pin "2") (pinfunction "2_2") (pintype "passive"))
      (node (ref "U8") (pin "10") (pinfunction "NC3_10") (pintype "passive"))
    )
    (net (code "110") (name "Net-(U8-VDDA)") (class "Default")
      (node (ref "C33") (pin "1") (pinfunction "1_1") (pintype "passive"))
      (node (ref "C39") (pin "2") (pinfunction "2_2") (pintype "passive"))
      (node (ref "R21") (pin "1") (pinfunction "1_1") (pintype "passive"))
      (node (ref "U8") (pin "12") (pinfunction "VDDA_12") (pintype "power_in"))
    )
    (net (code "111") (name "PGND") (class "Default")
      (node (ref "C1") (pin "1") (pinfunction "1_1") (pintype "passive"))
      (node (ref "C10") (pin "1") (pinfunction "1_1") (pintype "passive"))
      (node (ref "C11") (pin "1") (pinfunction "1_1") (pintype "passive"))
      (node (ref "C12") (pin "1") (pinfunction "1_1") (pintype "passive"))
      (node (ref "C13") (pin "1") (pinfunction "1_1") (pintype "passive"))
      (node (ref "C16") (pin "1") (pinfunction "1_1") (pintype "passive"))
      (node (ref "C20") (pin "1") (pinfunction "1_1") (pintype "passive"))
      (node (ref "C25") (pin "1") (pinfunction "1_1") (pintype "passive"))
      (node (ref "C27") (pin "1") (pinfunction "1_1") (pintype "passive"))
      (node (ref "C28") (pin "1") (pinfunction "1_1") (pintype "passive"))
      (node (ref "C30") (pin "1") (pinfunction "1_1") (pintype "passive"))
      (node (ref "C36") (pin "1") (pinfunction "1_1") (pintype "passive"))
      (node (ref "C4") (pin "1") (pinfunction "1_1") (pintype "passive"))
      (node (ref "C41") (pin "1") (pinfunction "1_1") (pintype "passive"))
      (node (ref "C44") (pin "1") (pinfunction "1_1") (pintype "passive"))
      (node (ref "C45") (pin "1") (pinfunction "1_1") (pintype "passive"))
      (node (ref "C47") (pin "1") (pinfunction "1_1") (pintype "passive"))
      (node (ref "C5") (pin "1") (pinfunction "1_1") (pintype "passive"))
      (node (ref "C6") (pin "1") (pinfunction "1_1") (pintype "passive"))
      (node (ref "C7") (pin "1") (pinfunction "1_1") (pintype "passive"))
      (node (ref "C70") (pin "1") (pinfunction "1_1") (pintype "passive"))
      (node (ref "C72") (pin "1") (pinfunction "1_1") (pintype "passive"))
      (node (ref "C8") (pin "1") (pinfunction "1_1") (pintype "passive"))
      (node (ref "C9") (pin "1") (pinfunction "1_1") (pintype "passive"))
      (node (ref "D12") (pin "2") (pinfunction "A_2") (pintype "passive"))
      (node (ref "D14") (pin "1") (pinfunction "K_1") (pintype "passive"))
      (node (ref "D15") (pin "1") (pinfunction "K_1") (pintype "passive"))
      (node (ref "D9") (pin "2") (pinfunction "A_2") (pintype "passive"))
      (node (ref "Q3") (pin "3") (pinfunction "S_3") (pintype "passive"))
      (node (ref "Q4") (pin "3") (pinfunction "S_3") (pintype "passive"))
      (node (ref "R11") (pin "1") (pinfunction "1_1") (pintype "passive"))
      (node (ref "R14") (pin "1") (pinfunction "1_1") (pintype "passive"))
      (node (ref "R22") (pin "1") (pinfunction "1_1") (pintype "passive"))
      (node (ref "R23") (pin "2") (pinfunction "2_2") (pintype "passive"))
    )
    (net (code "112") (name "VCC_3V3") (class "Default")
      (node (ref "Q_I2C1") (pin "1") (pinfunction "G_1") (pintype "passive"))
      (node (ref "Q_I2C2") (pin "1") (pinfunction "G_1") (pintype "passive"))
      (node (ref "R_SCL3") (pin "2") (pinfunction "2_2") (pintype "passive"))
      (node (ref "R_SDA3") (pin "2") (pinfunction "2_2") (pintype "passive"))
    )
    (net (code "113") (name "VIN_N") (class "Default")
      (node (ref "C1") (pin "2") (pinfunction "2_2") (pintype "passive"))
      (node (ref "C10") (pin "2") (pinfunction "2_2") (pintype "passive"))
      (node (ref "C11") (pin "2") (pinfunction "2_2") (pintype "passive"))
      (node (ref "C12") (pin "2") (pinfunction "2_2") (pintype "passive"))
      (node (ref "C13") (pin "2") (pinfunction "2_2") (pintype "passive"))
      (node (ref "C16") (pin "2") (pinfunction "2_2") (pintype "passive"))
      (node (ref "C20") (pin "2") (pinfunction "2_2") (pintype "passive"))
      (node (ref "C25") (pin "2") (pinfunction "2_2") (pintype "passive"))
      (node (ref "C27") (pin "2") (pinfunction "2_2") (pintype "passive"))
      (node (ref "C28") (pin "2") (pinfunction "2_2") (pintype "passive"))
      (node (ref "C30") (pin "2") (pinfunction "2_2") (pintype "passive"))
      (node (ref "C36") (pin "2") (pinfunction "2_2") (pintype "passive"))
      (node (ref "C4") (pin "2") (pinfunction "2_2") (pintype "passive"))
      (node (ref "C41") (pin "2") (pinfunction "2_2") (pintype "passive"))
      (node (ref "C44") (pin "2") (pinfunction "2_2") (pintype "passive"))
      (node (ref "C45") (pin "2") (pinfunction "2_2") (pintype "passive"))
      (node (ref "C47") (pin "2") (pinfunction "2_2") (pintype "passive"))
      (node (ref "C5") (pin "2") (pinfunction "2_2") (pintype "passive"))
      (node (ref "C6") (pin "2") (pinfunction "2_2") (pintype "passive"))
      (node (ref "C7") (pin "2") (pinfunction "2_2") (pintype "passive"))
      (node (ref "C70") (pin "2") (pinfunction "2_2") (pintype "passive"))
      (node (ref "C72") (pin "2") (pinfunction "2_2") (pintype "passive"))
      (node (ref "C8") (pin "2") (pinfunction "2_2") (pintype "passive"))
      (node (ref "C9") (pin "2") (pinfunction "2_2") (pintype "passive"))
      (node (ref "D13") (pin "1") (pinfunction "K_1") (pintype "passive"))
      (node (ref "Q1") (pin "2") (pinfunction "D_2") (pintype "passive"))
      (node (ref "R1") (pin "1") (pinfunction "1_1") (pintype "passive"))
      (node (ref "R13") (pin "2") (pinfunction "2_2") (pintype "passive"))
      (node (ref "RB1_P") (pin "1") (pinfunction "1_1") (pintype "passive"))
    )
    (net (code "114") (name "VIN_P") (class "Default")
      (node (ref "C21") (pin "2") (pinfunction "2_2") (pintype "passive"))
      (node (ref "C22") (pin "2") (pinfunction "2_2") (pintype "passive"))
      (node (ref "C26") (pin "2") (pinfunction "2_2") (pintype "passive"))
      (node (ref "C64") (pin "2") (pinfunction "2_2") (pintype "passive"))
      (node (ref "D1_a") (pin "1") (pinfunction "K_1") (pintype "passive"))
      (node (ref "D1_b") (pin "1") (pinfunction "K_1") (pintype "passive"))
      (node (ref "D1_c") (pin "1") (pinfunction "K_1") (pintype "passive"))
      (node (ref "D1_d") (pin "1") (pinfunction "K_1") (pintype "passive"))
      (node (ref "D1_e") (pin "1") (pinfunction "K_1") (pintype "passive"))
      (node (ref "D1_f") (pin "1") (pinfunction "K_1") (pintype "passive"))
      (node (ref "D2_a") (pin "1") (pinfunction "K_1") (pintype "passive"))
      (node (ref "D2_b") (pin "1") (pinfunction "K_1") (pintype "passive"))
      (node (ref "D2_c") (pin "1") (pinfunction "K_1") (pintype "passive"))
      (node (ref "D2_d") (pin "1") (pinfunction "K_1") (pintype "passive"))
      (node (ref "D2_e") (pin "1") (pinfunction "K_1") (pintype "passive"))
      (node (ref "D2_f") (pin "1") (pinfunction "K_1") (pintype "passive"))
      (node (ref "D_CLAMP_1") (pin "1") (pinfunction "K_1") (pintype "passive"))
      (node (ref "R1") (pin "2") (pinfunction "2_2") (pintype "passive"))
      (node (ref "RB1_N") (pin "1") (pinfunction "1_1") (pintype "passive"))
      (node (ref "Ron_c") (pin "1") (pinfunction "1_1") (pintype "passive"))
      (node (ref "Ron_d") (pin "1") (pinfunction "1_1") (pintype "passive"))
      (node (ref "U1") (pin "8") (pinfunction "VIN_8") (pintype "input"))
    )
    (net (code "115") (name "VOUT_P") (class "Default")
      (node (ref "D7") (pin "1") (pinfunction "K_1") (pintype "passive"))
      (node (ref "Q2") (pin "2") (pinfunction "D_2") (pintype "passive"))
      (node (ref "R10") (pin "1") (pinfunction "1_1") (pintype "passive"))
      (node (ref "R51") (pin "2") (pinfunction "2_2") (pintype "passive"))
      (node (ref "RA1_P") (pin "1") (pinfunction "1_1") (pintype "passive"))
    )
    (net (code "116") (name "unconnected-(J_IN-PadM)") (class "Default")
      (node (ref "J_IN") (pin "M") (pinfunction "M_M") (pintype "passive"))
    )
    (net (code "117") (name "unconnected-(J_OUT-PadM)") (class "Default")
      (node (ref "J_OUT") (pin "M") (pinfunction "M_M") (pintype "passive"))
    )
    (net (code "118") (name "unconnected-(U7-OVP-Pad15)") (class "Default")
      (node (ref "U7") (pin "15") (pinfunction "OVP_15") (pintype "passive"))
    )
    (net (code "119") (name "unconnected-(U8-PM_OUT-Pad11)") (class "Default")
      (node (ref "U8") (pin "11") (pinfunction "PM_OUT_11") (pintype "output"))
    )
  )
)
